# zok-atmega644-bob.net
KiCad netlist of a schematic drawn in EAGLE
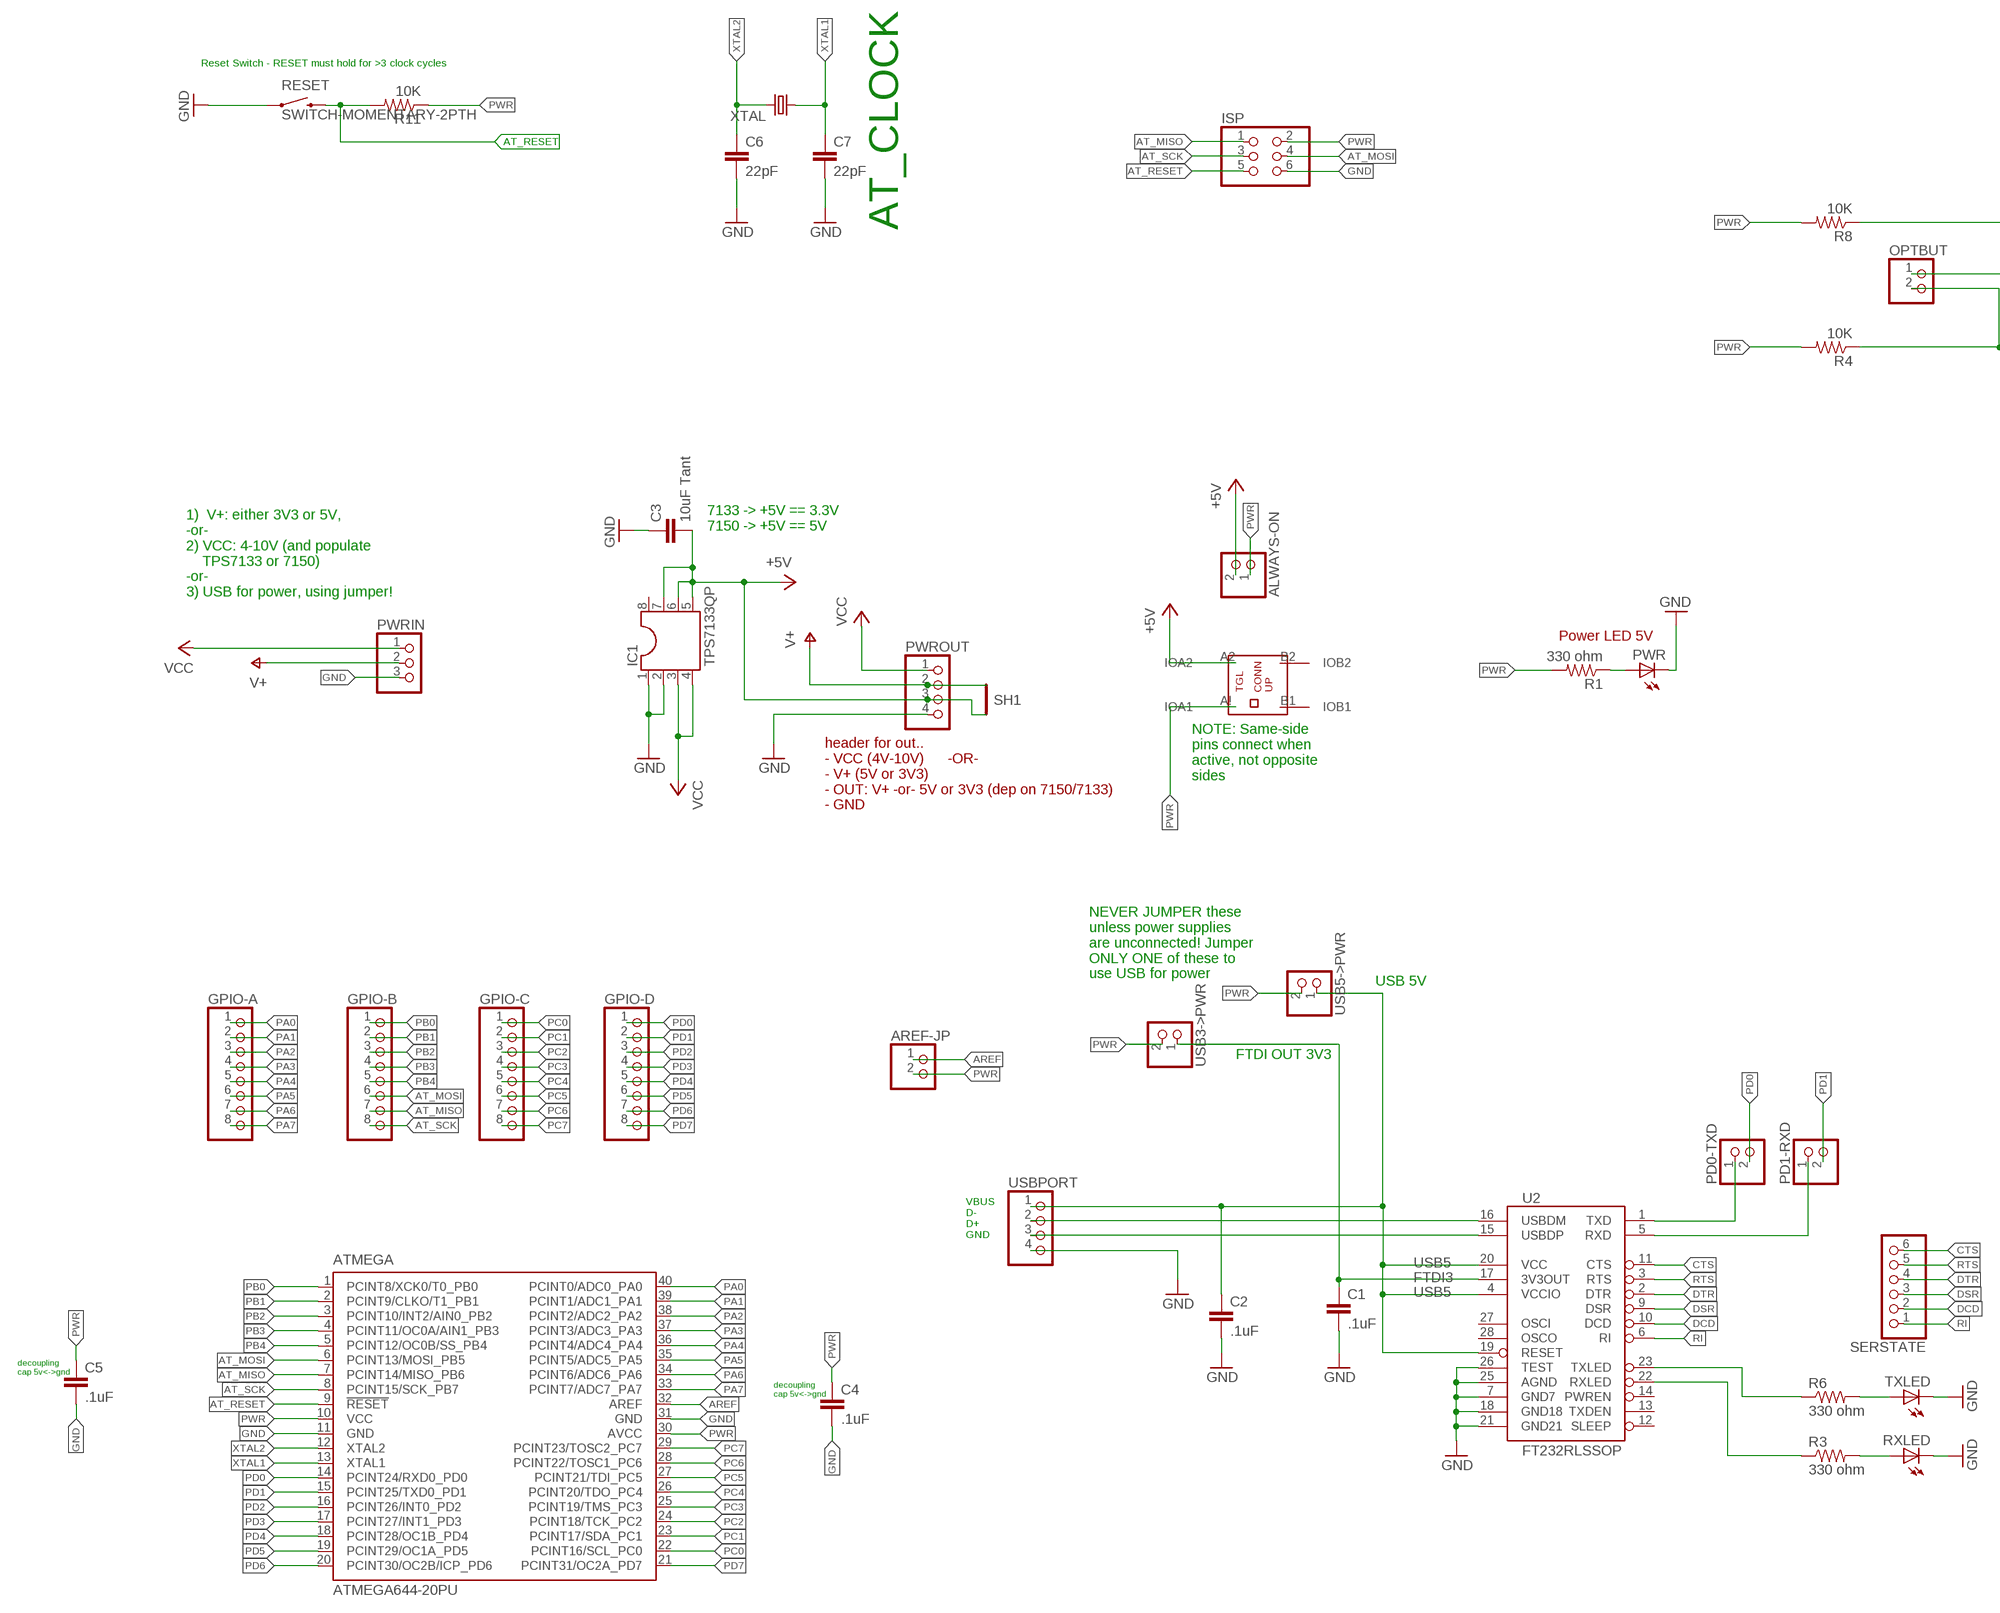
[diagram p0: schematic, sheet 1, part 1 of 2]
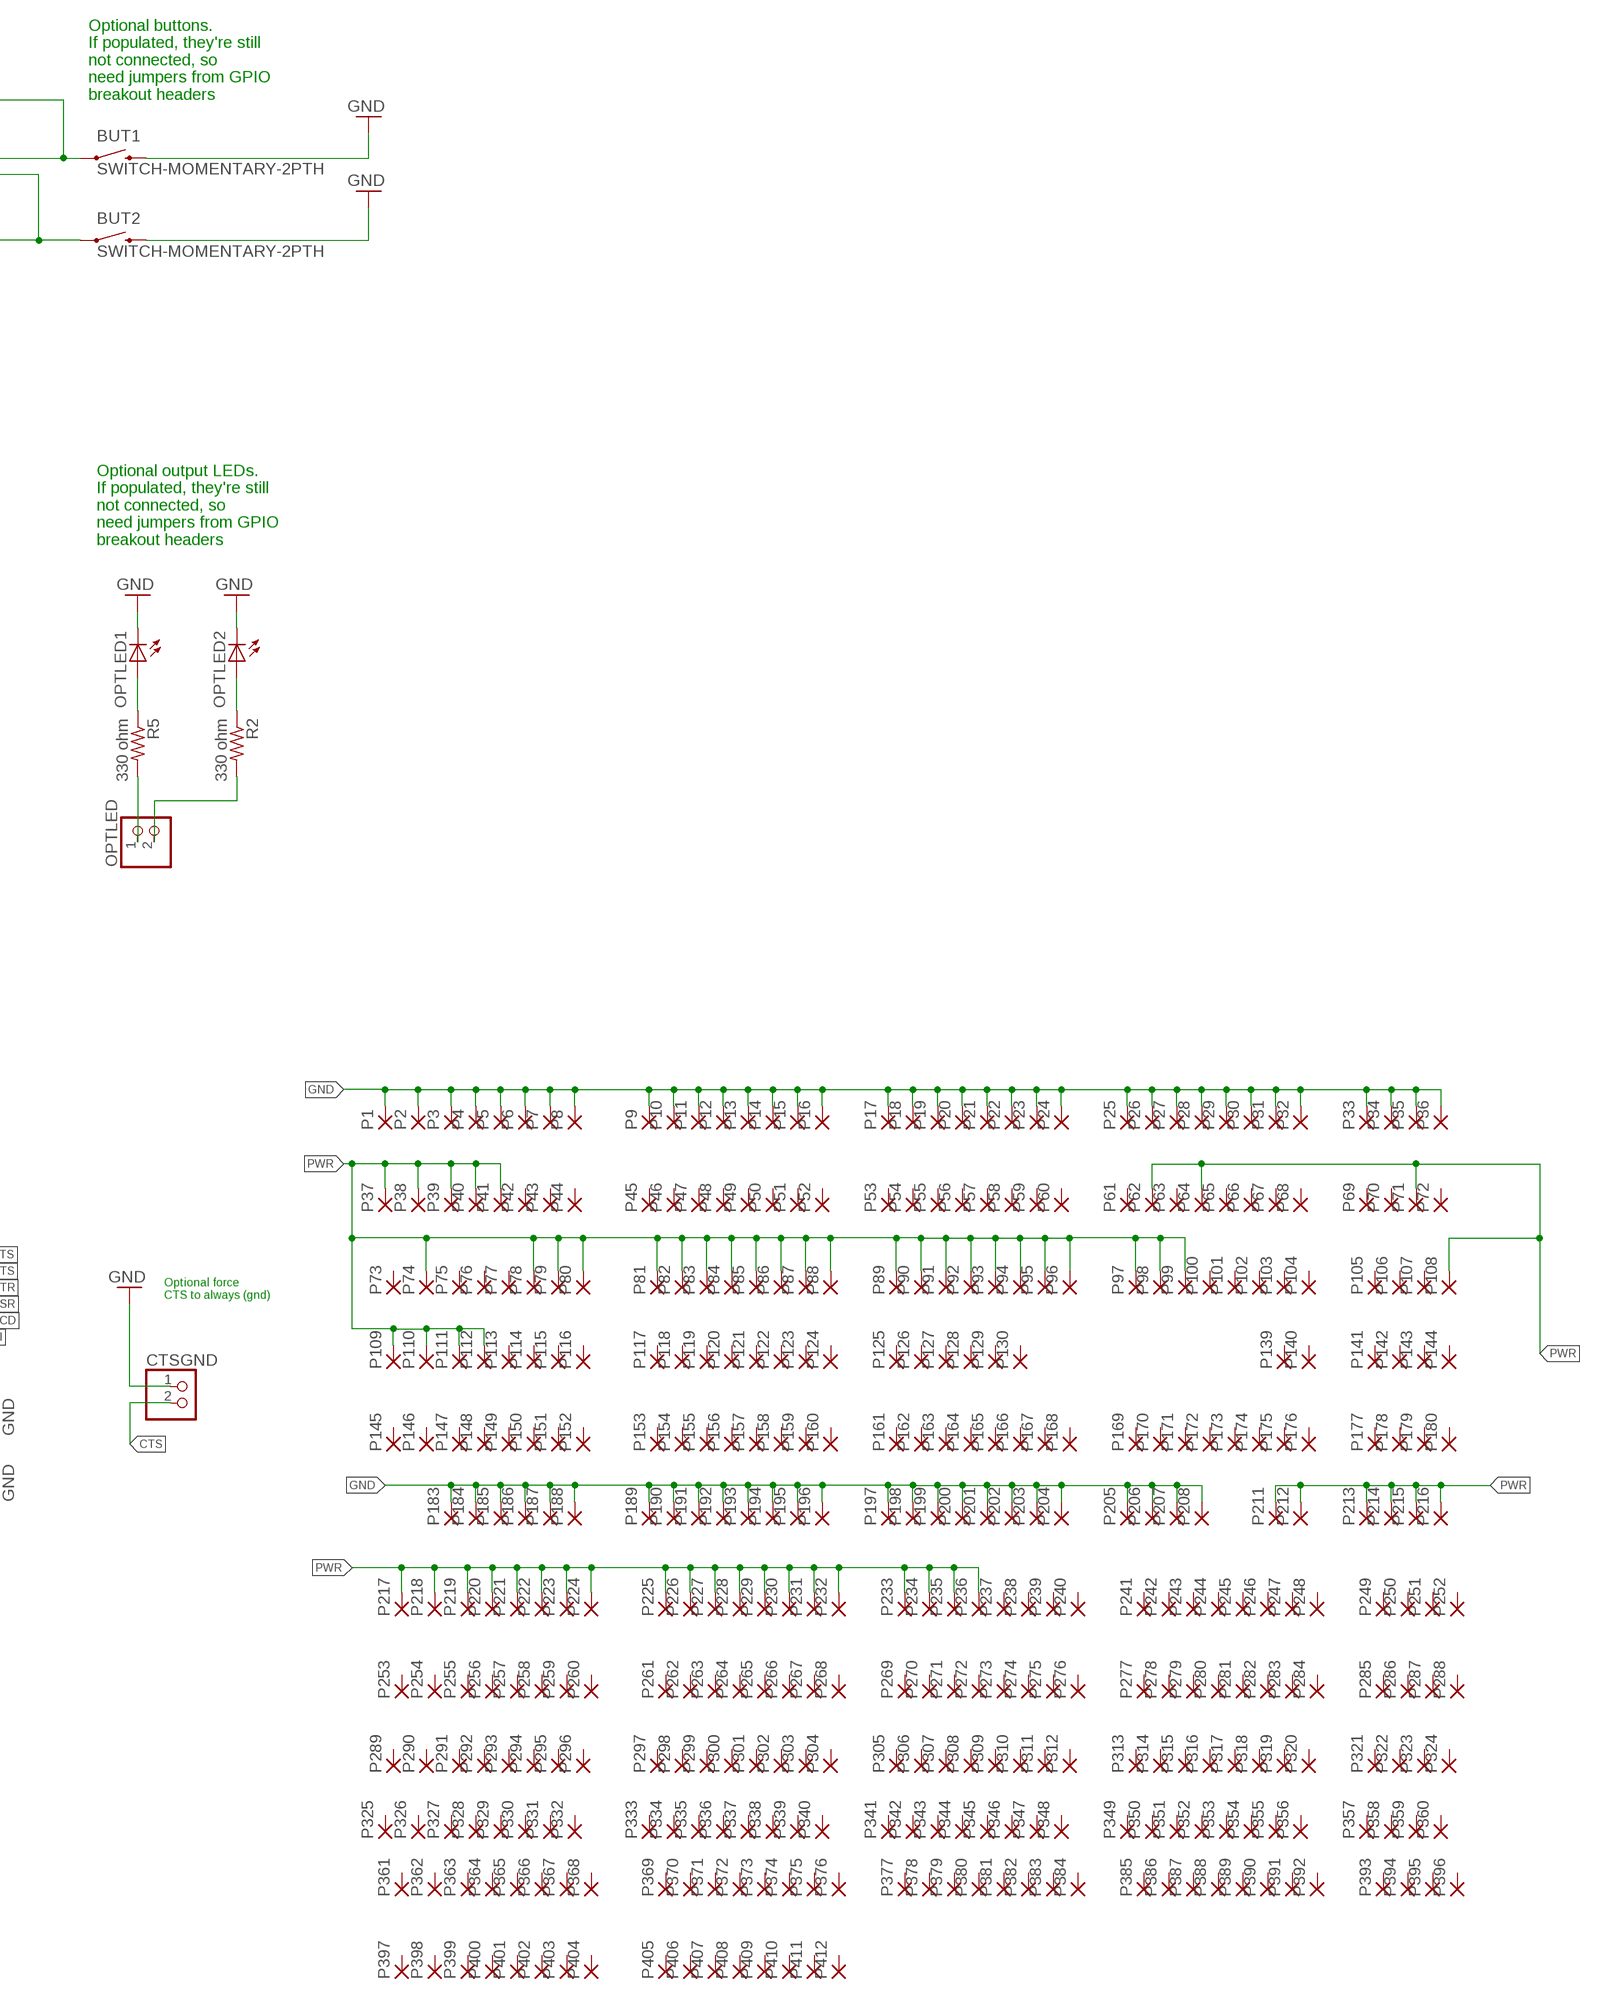
[diagram p1: schematic, sheet 1, part 2 of 2]

(export (version "E")
  (design (tool "Eeschema 10.0.6"))
  (components
    (comp (ref "ALWAYS-ON")
      (value "PINHD-1X2")
      (footprint "eagle-import:1X02")
      (libsource (lib "eagle-import") (part "PINHD-1X2"))
    )
    (comp (ref "AREF-JP")
      (value "PINHD-1X2")
      (footprint "eagle-import:1X02")
      (libsource (lib "eagle-import") (part "PINHD-1X2"))
    )
    (comp (ref "ATMEGA")
      (value "ATMEGA644-20PU")
      (footprint "eagle-import:DIL40")
      (libsource (lib "eagle-import") (part "ATMEGA644-PU20"))
    )
    (comp (ref "BUT1")
      (value "SWITCH-MOMENTARY-2PTH")
      (footprint "eagle-import:TACTILE-PTH")
      (libsource (lib "eagle-import") (part "SWITCH-MOMENTARY-2PTH"))
    )
    (comp (ref "BUT2")
      (value "SWITCH-MOMENTARY-2PTH")
      (footprint "eagle-import:TACTILE-PTH")
      (libsource (lib "eagle-import") (part "SWITCH-MOMENTARY-2PTH"))
    )
    (comp (ref "C1")
      (value ".1uF")
      (footprint "eagle-import:C025-025X050")
      (libsource (lib "eagle-import") (part "C-EU025-025X050"))
    )
    (comp (ref "C2")
      (value ".1uF")
      (footprint "eagle-import:C025-025X050")
      (libsource (lib "eagle-import") (part "C-EU025-025X050"))
    )
    (comp (ref "C3")
      (value "10uF Tant")
      (footprint "eagle-import:C025-025X050")
      (libsource (lib "eagle-import") (part "C-EU025-025X050"))
    )
    (comp (ref "C4")
      (value ".1uF")
      (footprint "eagle-import:C025-025X050")
      (libsource (lib "eagle-import") (part "C-EU025-025X050"))
    )
    (comp (ref "C5")
      (value ".1uF")
      (footprint "eagle-import:C025-025X050")
      (libsource (lib "eagle-import") (part "C-EU025-025X050"))
    )
    (comp (ref "C6")
      (value "22pF")
      (footprint "eagle-import:C025-025X050")
      (libsource (lib "eagle-import") (part "C-EU025-025X050"))
    )
    (comp (ref "C7")
      (value "22pF")
      (footprint "eagle-import:C025-025X050")
      (libsource (lib "eagle-import") (part "C-EU025-025X050"))
    )
    (comp (ref "CTSGND")
      (value "PINHD-1X2")
      (footprint "eagle-import:1X02")
      (libsource (lib "eagle-import") (part "PINHD-1X2"))
    )
    (comp (ref "GPIO-A")
      (value "PINHD-1X8")
      (footprint "eagle-import:1X08")
      (libsource (lib "eagle-import") (part "PINHD-1X8"))
    )
    (comp (ref "GPIO-B")
      (value "PINHD-1X8")
      (footprint "eagle-import:1X08")
      (libsource (lib "eagle-import") (part "PINHD-1X8"))
    )
    (comp (ref "GPIO-C")
      (value "PINHD-1X8")
      (footprint "eagle-import:1X08")
      (libsource (lib "eagle-import") (part "PINHD-1X8"))
    )
    (comp (ref "GPIO-D")
      (value "PINHD-1X8")
      (footprint "eagle-import:1X08")
      (libsource (lib "eagle-import") (part "PINHD-1X8"))
    )
    (comp (ref "IC1")
      (value "TPS7133QP")
      (footprint "eagle-import:DIL08")
      (libsource (lib "eagle-import") (part "DIL8"))
    )
    (comp (ref "ISP")
      (value "PINHD-2X3")
      (footprint "eagle-import:2X03")
      (libsource (lib "eagle-import") (part "PINHD-2X3"))
    )
    (comp (ref "OPTBUT")
      (value "PINHD-1X2")
      (footprint "eagle-import:1X02")
      (libsource (lib "eagle-import") (part "PINHD-1X2"))
    )
    (comp (ref "OPTLED")
      (value "PINHD-1X2")
      (footprint "eagle-import:1X02")
      (libsource (lib "eagle-import") (part "PINHD-1X2"))
    )
    (comp (ref "OPTLED1")
      (value "LED5MM")
      (footprint "eagle-import:LED5MM")
      (libsource (lib "eagle-import") (part "LED5MM"))
    )
    (comp (ref "OPTLED2")
      (value "LED5MM")
      (footprint "eagle-import:LED5MM")
      (libsource (lib "eagle-import") (part "LED5MM"))
    )
    (comp (ref "P1")
      (value "1,6/0,9")
      (footprint "eagle-import:1,6_0,9")
      (libsource (lib "eagle-import") (part "1,6/0,9"))
    )
    (comp (ref "P2")
      (value "1,6/0,9")
      (footprint "eagle-import:1,6_0,9")
      (libsource (lib "eagle-import") (part "1,6/0,9"))
    )
    (comp (ref "P3")
      (value "1,6/0,9")
      (footprint "eagle-import:1,6_0,9")
      (libsource (lib "eagle-import") (part "1,6/0,9"))
    )
    (comp (ref "P4")
      (value "1,6/0,9")
      (footprint "eagle-import:1,6_0,9")
      (libsource (lib "eagle-import") (part "1,6/0,9"))
    )
    (comp (ref "P5")
      (value "1,6/0,9")
      (footprint "eagle-import:1,6_0,9")
      (libsource (lib "eagle-import") (part "1,6/0,9"))
    )
    (comp (ref "P6")
      (value "1,6/0,9")
      (footprint "eagle-import:1,6_0,9")
      (libsource (lib "eagle-import") (part "1,6/0,9"))
    )
    (comp (ref "P7")
      (value "1,6/0,9")
      (footprint "eagle-import:1,6_0,9")
      (libsource (lib "eagle-import") (part "1,6/0,9"))
    )
    (comp (ref "P8")
      (value "1,6/0,9")
      (footprint "eagle-import:1,6_0,9")
      (libsource (lib "eagle-import") (part "1,6/0,9"))
    )
    (comp (ref "P9")
      (value "1,6/0,9")
      (footprint "eagle-import:1,6_0,9")
      (libsource (lib "eagle-import") (part "1,6/0,9"))
    )
    (comp (ref "P10")
      (value "1,6/0,9")
      (footprint "eagle-import:1,6_0,9")
      (libsource (lib "eagle-import") (part "1,6/0,9"))
    )
    (comp (ref "P11")
      (value "1,6/0,9")
      (footprint "eagle-import:1,6_0,9")
      (libsource (lib "eagle-import") (part "1,6/0,9"))
    )
    (comp (ref "P12")
      (value "1,6/0,9")
      (footprint "eagle-import:1,6_0,9")
      (libsource (lib "eagle-import") (part "1,6/0,9"))
    )
    (comp (ref "P13")
      (value "1,6/0,9")
      (footprint "eagle-import:1,6_0,9")
      (libsource (lib "eagle-import") (part "1,6/0,9"))
    )
    (comp (ref "P14")
      (value "1,6/0,9")
      (footprint "eagle-import:1,6_0,9")
      (libsource (lib "eagle-import") (part "1,6/0,9"))
    )
    (comp (ref "P15")
      (value "1,6/0,9")
      (footprint "eagle-import:1,6_0,9")
      (libsource (lib "eagle-import") (part "1,6/0,9"))
    )
    (comp (ref "P16")
      (value "1,6/0,9")
      (footprint "eagle-import:1,6_0,9")
      (libsource (lib "eagle-import") (part "1,6/0,9"))
    )
    (comp (ref "P17")
      (value "1,6/0,9")
      (footprint "eagle-import:1,6_0,9")
      (libsource (lib "eagle-import") (part "1,6/0,9"))
    )
    (comp (ref "P18")
      (value "1,6/0,9")
      (footprint "eagle-import:1,6_0,9")
      (libsource (lib "eagle-import") (part "1,6/0,9"))
    )
    (comp (ref "P19")
      (value "1,6/0,9")
      (footprint "eagle-import:1,6_0,9")
      (libsource (lib "eagle-import") (part "1,6/0,9"))
    )
    (comp (ref "P20")
      (value "1,6/0,9")
      (footprint "eagle-import:1,6_0,9")
      (libsource (lib "eagle-import") (part "1,6/0,9"))
    )
    (comp (ref "P21")
      (value "1,6/0,9")
      (footprint "eagle-import:1,6_0,9")
      (libsource (lib "eagle-import") (part "1,6/0,9"))
    )
    (comp (ref "P22")
      (value "1,6/0,9")
      (footprint "eagle-import:1,6_0,9")
      (libsource (lib "eagle-import") (part "1,6/0,9"))
    )
    (comp (ref "P23")
      (value "1,6/0,9")
      (footprint "eagle-import:1,6_0,9")
      (libsource (lib "eagle-import") (part "1,6/0,9"))
    )
    (comp (ref "P24")
      (value "1,6/0,9")
      (footprint "eagle-import:1,6_0,9")
      (libsource (lib "eagle-import") (part "1,6/0,9"))
    )
    (comp (ref "P25")
      (value "1,6/0,9")
      (footprint "eagle-import:1,6_0,9")
      (libsource (lib "eagle-import") (part "1,6/0,9"))
    )
    (comp (ref "P26")
      (value "1,6/0,9")
      (footprint "eagle-import:1,6_0,9")
      (libsource (lib "eagle-import") (part "1,6/0,9"))
    )
    (comp (ref "P27")
      (value "1,6/0,9")
      (footprint "eagle-import:1,6_0,9")
      (libsource (lib "eagle-import") (part "1,6/0,9"))
    )
    (comp (ref "P28")
      (value "1,6/0,9")
      (footprint "eagle-import:1,6_0,9")
      (libsource (lib "eagle-import") (part "1,6/0,9"))
    )
    (comp (ref "P29")
      (value "1,6/0,9")
      (footprint "eagle-import:1,6_0,9")
      (libsource (lib "eagle-import") (part "1,6/0,9"))
    )
    (comp (ref "P30")
      (value "1,6/0,9")
      (footprint "eagle-import:1,6_0,9")
      (libsource (lib "eagle-import") (part "1,6/0,9"))
    )
    (comp (ref "P31")
      (value "1,6/0,9")
      (footprint "eagle-import:1,6_0,9")
      (libsource (lib "eagle-import") (part "1,6/0,9"))
    )
    (comp (ref "P32")
      (value "1,6/0,9")
      (footprint "eagle-import:1,6_0,9")
      (libsource (lib "eagle-import") (part "1,6/0,9"))
    )
    (comp (ref "P33")
      (value "1,6/0,9")
      (footprint "eagle-import:1,6_0,9")
      (libsource (lib "eagle-import") (part "1,6/0,9"))
    )
    (comp (ref "P34")
      (value "1,6/0,9")
      (footprint "eagle-import:1,6_0,9")
      (libsource (lib "eagle-import") (part "1,6/0,9"))
    )
    (comp (ref "P35")
      (value "1,6/0,9")
      (footprint "eagle-import:1,6_0,9")
      (libsource (lib "eagle-import") (part "1,6/0,9"))
    )
    (comp (ref "P36")
      (value "1,6/0,9")
      (footprint "eagle-import:1,6_0,9")
      (libsource (lib "eagle-import") (part "1,6/0,9"))
    )
    (comp (ref "P37")
      (value "1,6/0,9")
      (footprint "eagle-import:1,6_0,9")
      (libsource (lib "eagle-import") (part "1,6/0,9"))
    )
    (comp (ref "P38")
      (value "1,6/0,9")
      (footprint "eagle-import:1,6_0,9")
      (libsource (lib "eagle-import") (part "1,6/0,9"))
    )
    (comp (ref "P39")
      (value "1,6/0,9")
      (footprint "eagle-import:1,6_0,9")
      (libsource (lib "eagle-import") (part "1,6/0,9"))
    )
    (comp (ref "P40")
      (value "1,6/0,9")
      (footprint "eagle-import:1,6_0,9")
      (libsource (lib "eagle-import") (part "1,6/0,9"))
    )
    (comp (ref "P41")
      (value "1,6/0,9")
      (footprint "eagle-import:1,6_0,9")
      (libsource (lib "eagle-import") (part "1,6/0,9"))
    )
    (comp (ref "P42")
      (value "1,6/0,9")
      (footprint "eagle-import:1,6_0,9")
      (libsource (lib "eagle-import") (part "1,6/0,9"))
    )
    (comp (ref "P43")
      (value "1,6/0,9")
      (footprint "eagle-import:1,6_0,9")
      (libsource (lib "eagle-import") (part "1,6/0,9"))
    )
    (comp (ref "P44")
      (value "1,6/0,9")
      (footprint "eagle-import:1,6_0,9")
      (libsource (lib "eagle-import") (part "1,6/0,9"))
    )
    (comp (ref "P45")
      (value "1,6/0,9")
      (footprint "eagle-import:1,6_0,9")
      (libsource (lib "eagle-import") (part "1,6/0,9"))
    )
    (comp (ref "P46")
      (value "1,6/0,9")
      (footprint "eagle-import:1,6_0,9")
      (libsource (lib "eagle-import") (part "1,6/0,9"))
    )
    (comp (ref "P47")
      (value "1,6/0,9")
      (footprint "eagle-import:1,6_0,9")
      (libsource (lib "eagle-import") (part "1,6/0,9"))
    )
    (comp (ref "P48")
      (value "1,6/0,9")
      (footprint "eagle-import:1,6_0,9")
      (libsource (lib "eagle-import") (part "1,6/0,9"))
    )
    (comp (ref "P49")
      (value "1,6/0,9")
      (footprint "eagle-import:1,6_0,9")
      (libsource (lib "eagle-import") (part "1,6/0,9"))
    )
    (comp (ref "P50")
      (value "1,6/0,9")
      (footprint "eagle-import:1,6_0,9")
      (libsource (lib "eagle-import") (part "1,6/0,9"))
    )
    (comp (ref "P51")
      (value "1,6/0,9")
      (footprint "eagle-import:1,6_0,9")
      (libsource (lib "eagle-import") (part "1,6/0,9"))
    )
    (comp (ref "P52")
      (value "1,6/0,9")
      (footprint "eagle-import:1,6_0,9")
      (libsource (lib "eagle-import") (part "1,6/0,9"))
    )
    (comp (ref "P53")
      (value "1,6/0,9")
      (footprint "eagle-import:1,6_0,9")
      (libsource (lib "eagle-import") (part "1,6/0,9"))
    )
    (comp (ref "P54")
      (value "1,6/0,9")
      (footprint "eagle-import:1,6_0,9")
      (libsource (lib "eagle-import") (part "1,6/0,9"))
    )
    (comp (ref "P55")
      (value "1,6/0,9")
      (footprint "eagle-import:1,6_0,9")
      (libsource (lib "eagle-import") (part "1,6/0,9"))
    )
    (comp (ref "P56")
      (value "1,6/0,9")
      (footprint "eagle-import:1,6_0,9")
      (libsource (lib "eagle-import") (part "1,6/0,9"))
    )
    (comp (ref "P57")
      (value "1,6/0,9")
      (footprint "eagle-import:1,6_0,9")
      (libsource (lib "eagle-import") (part "1,6/0,9"))
    )
    (comp (ref "P58")
      (value "1,6/0,9")
      (footprint "eagle-import:1,6_0,9")
      (libsource (lib "eagle-import") (part "1,6/0,9"))
    )
    (comp (ref "P59")
      (value "1,6/0,9")
      (footprint "eagle-import:1,6_0,9")
      (libsource (lib "eagle-import") (part "1,6/0,9"))
    )
    (comp (ref "P60")
      (value "1,6/0,9")
      (footprint "eagle-import:1,6_0,9")
      (libsource (lib "eagle-import") (part "1,6/0,9"))
    )
    (comp (ref "P61")
      (value "1,6/0,9")
      (footprint "eagle-import:1,6_0,9")
      (libsource (lib "eagle-import") (part "1,6/0,9"))
    )
    (comp (ref "P62")
      (value "1,6/0,9")
      (footprint "eagle-import:1,6_0,9")
      (libsource (lib "eagle-import") (part "1,6/0,9"))
    )
    (comp (ref "P63")
      (value "1,6/0,9")
      (footprint "eagle-import:1,6_0,9")
      (libsource (lib "eagle-import") (part "1,6/0,9"))
    )
    (comp (ref "P64")
      (value "1,6/0,9")
      (footprint "eagle-import:1,6_0,9")
      (libsource (lib "eagle-import") (part "1,6/0,9"))
    )
    (comp (ref "P65")
      (value "1,6/0,9")
      (footprint "eagle-import:1,6_0,9")
      (libsource (lib "eagle-import") (part "1,6/0,9"))
    )
    (comp (ref "P66")
      (value "1,6/0,9")
      (footprint "eagle-import:1,6_0,9")
      (libsource (lib "eagle-import") (part "1,6/0,9"))
    )
    (comp (ref "P67")
      (value "1,6/0,9")
      (footprint "eagle-import:1,6_0,9")
      (libsource (lib "eagle-import") (part "1,6/0,9"))
    )
    (comp (ref "P68")
      (value "1,6/0,9")
      (footprint "eagle-import:1,6_0,9")
      (libsource (lib "eagle-import") (part "1,6/0,9"))
    )
    (comp (ref "P69")
      (value "1,6/0,9")
      (footprint "eagle-import:1,6_0,9")
      (libsource (lib "eagle-import") (part "1,6/0,9"))
    )
    (comp (ref "P70")
      (value "1,6/0,9")
      (footprint "eagle-import:1,6_0,9")
      (libsource (lib "eagle-import") (part "1,6/0,9"))
    )
    (comp (ref "P71")
      (value "1,6/0,9")
      (footprint "eagle-import:1,6_0,9")
      (libsource (lib "eagle-import") (part "1,6/0,9"))
    )
    (comp (ref "P72")
      (value "1,6/0,9")
      (footprint "eagle-import:1,6_0,9")
      (libsource (lib "eagle-import") (part "1,6/0,9"))
    )
    (comp (ref "P73")
      (value "1,6/0,9")
      (footprint "eagle-import:1,6_0,9")
      (libsource (lib "eagle-import") (part "1,6/0,9"))
    )
    (comp (ref "P74")
      (value "1,6/0,9")
      (footprint "eagle-import:1,6_0,9")
      (libsource (lib "eagle-import") (part "1,6/0,9"))
    )
    (comp (ref "P75")
      (value "1,6/0,9")
      (footprint "eagle-import:1,6_0,9")
      (libsource (lib "eagle-import") (part "1,6/0,9"))
    )
    (comp (ref "P76")
      (value "1,6/0,9")
      (footprint "eagle-import:1,6_0,9")
      (libsource (lib "eagle-import") (part "1,6/0,9"))
    )
    (comp (ref "P77")
      (value "1,6/0,9")
      (footprint "eagle-import:1,6_0,9")
      (libsource (lib "eagle-import") (part "1,6/0,9"))
    )
    (comp (ref "P78")
      (value "1,6/0,9")
      (footprint "eagle-import:1,6_0,9")
      (libsource (lib "eagle-import") (part "1,6/0,9"))
    )
    (comp (ref "P79")
      (value "1,6/0,9")
      (footprint "eagle-import:1,6_0,9")
      (libsource (lib "eagle-import") (part "1,6/0,9"))
    )
    (comp (ref "P80")
      (value "1,6/0,9")
      (footprint "eagle-import:1,6_0,9")
      (libsource (lib "eagle-import") (part "1,6/0,9"))
    )
    (comp (ref "P81")
      (value "1,6/0,9")
      (footprint "eagle-import:1,6_0,9")
      (libsource (lib "eagle-import") (part "1,6/0,9"))
    )
    (comp (ref "P82")
      (value "1,6/0,9")
      (footprint "eagle-import:1,6_0,9")
      (libsource (lib "eagle-import") (part "1,6/0,9"))
    )
    (comp (ref "P83")
      (value "1,6/0,9")
      (footprint "eagle-import:1,6_0,9")
      (libsource (lib "eagle-import") (part "1,6/0,9"))
    )
    (comp (ref "P84")
      (value "1,6/0,9")
      (footprint "eagle-import:1,6_0,9")
      (libsource (lib "eagle-import") (part "1,6/0,9"))
    )
    (comp (ref "P85")
      (value "1,6/0,9")
      (footprint "eagle-import:1,6_0,9")
      (libsource (lib "eagle-import") (part "1,6/0,9"))
    )
    (comp (ref "P86")
      (value "1,6/0,9")
      (footprint "eagle-import:1,6_0,9")
      (libsource (lib "eagle-import") (part "1,6/0,9"))
    )
    (comp (ref "P87")
      (value "1,6/0,9")
      (footprint "eagle-import:1,6_0,9")
      (libsource (lib "eagle-import") (part "1,6/0,9"))
    )
    (comp (ref "P88")
      (value "1,6/0,9")
      (footprint "eagle-import:1,6_0,9")
      (libsource (lib "eagle-import") (part "1,6/0,9"))
    )
    (comp (ref "P89")
      (value "1,6/0,9")
      (footprint "eagle-import:1,6_0,9")
      (libsource (lib "eagle-import") (part "1,6/0,9"))
    )
    (comp (ref "P90")
      (value "1,6/0,9")
      (footprint "eagle-import:1,6_0,9")
      (libsource (lib "eagle-import") (part "1,6/0,9"))
    )
    (comp (ref "P91")
      (value "1,6/0,9")
      (footprint "eagle-import:1,6_0,9")
      (libsource (lib "eagle-import") (part "1,6/0,9"))
    )
    (comp (ref "P92")
      (value "1,6/0,9")
      (footprint "eagle-import:1,6_0,9")
      (libsource (lib "eagle-import") (part "1,6/0,9"))
    )
    (comp (ref "P93")
      (value "1,6/0,9")
      (footprint "eagle-import:1,6_0,9")
      (libsource (lib "eagle-import") (part "1,6/0,9"))
    )
    (comp (ref "P94")
      (value "1,6/0,9")
      (footprint "eagle-import:1,6_0,9")
      (libsource (lib "eagle-import") (part "1,6/0,9"))
    )
    (comp (ref "P95")
      (value "1,6/0,9")
      (footprint "eagle-import:1,6_0,9")
      (libsource (lib "eagle-import") (part "1,6/0,9"))
    )
    (comp (ref "P96")
      (value "1,6/0,9")
      (footprint "eagle-import:1,6_0,9")
      (libsource (lib "eagle-import") (part "1,6/0,9"))
    )
    (comp (ref "P97")
      (value "1,6/0,9")
      (footprint "eagle-import:1,6_0,9")
      (libsource (lib "eagle-import") (part "1,6/0,9"))
    )
    (comp (ref "P98")
      (value "1,6/0,9")
      (footprint "eagle-import:1,6_0,9")
      (libsource (lib "eagle-import") (part "1,6/0,9"))
    )
    (comp (ref "P99")
      (value "1,6/0,9")
      (footprint "eagle-import:1,6_0,9")
      (libsource (lib "eagle-import") (part "1,6/0,9"))
    )
    (comp (ref "P100")
      (value "1,6/0,9")
      (footprint "eagle-import:1,6_0,9")
      (libsource (lib "eagle-import") (part "1,6/0,9"))
    )
    (comp (ref "P101")
      (value "1,6/0,9")
      (footprint "eagle-import:1,6_0,9")
      (libsource (lib "eagle-import") (part "1,6/0,9"))
    )
    (comp (ref "P102")
      (value "1,6/0,9")
      (footprint "eagle-import:1,6_0,9")
      (libsource (lib "eagle-import") (part "1,6/0,9"))
    )
    (comp (ref "P103")
      (value "1,6/0,9")
      (footprint "eagle-import:1,6_0,9")
      (libsource (lib "eagle-import") (part "1,6/0,9"))
    )
    (comp (ref "P104")
      (value "1,6/0,9")
      (footprint "eagle-import:1,6_0,9")
      (libsource (lib "eagle-import") (part "1,6/0,9"))
    )
    (comp (ref "P105")
      (value "1,6/0,9")
      (footprint "eagle-import:1,6_0,9")
      (libsource (lib "eagle-import") (part "1,6/0,9"))
    )
    (comp (ref "P106")
      (value "1,6/0,9")
      (footprint "eagle-import:1,6_0,9")
      (libsource (lib "eagle-import") (part "1,6/0,9"))
    )
    (comp (ref "P107")
      (value "1,6/0,9")
      (footprint "eagle-import:1,6_0,9")
      (libsource (lib "eagle-import") (part "1,6/0,9"))
    )
    (comp (ref "P108")
      (value "1,6/0,9")
      (footprint "eagle-import:1,6_0,9")
      (libsource (lib "eagle-import") (part "1,6/0,9"))
    )
    (comp (ref "P109")
      (value "1,6/0,9")
      (footprint "eagle-import:1,6_0,9")
      (libsource (lib "eagle-import") (part "1,6/0,9"))
    )
    (comp (ref "P110")
      (value "1,6/0,9")
      (footprint "eagle-import:1,6_0,9")
      (libsource (lib "eagle-import") (part "1,6/0,9"))
    )
    (comp (ref "P111")
      (value "1,6/0,9")
      (footprint "eagle-import:1,6_0,9")
      (libsource (lib "eagle-import") (part "1,6/0,9"))
    )
    (comp (ref "P112")
      (value "1,6/0,9")
      (footprint "eagle-import:1,6_0,9")
      (libsource (lib "eagle-import") (part "1,6/0,9"))
    )
    (comp (ref "P113")
      (value "1,6/0,9")
      (footprint "eagle-import:1,6_0,9")
      (libsource (lib "eagle-import") (part "1,6/0,9"))
    )
    (comp (ref "P114")
      (value "1,6/0,9")
      (footprint "eagle-import:1,6_0,9")
      (libsource (lib "eagle-import") (part "1,6/0,9"))
    )
    (comp (ref "P115")
      (value "1,6/0,9")
      (footprint "eagle-import:1,6_0,9")
      (libsource (lib "eagle-import") (part "1,6/0,9"))
    )
    (comp (ref "P116")
      (value "1,6/0,9")
      (footprint "eagle-import:1,6_0,9")
      (libsource (lib "eagle-import") (part "1,6/0,9"))
    )
    (comp (ref "P117")
      (value "1,6/0,9")
      (footprint "eagle-import:1,6_0,9")
      (libsource (lib "eagle-import") (part "1,6/0,9"))
    )
    (comp (ref "P118")
      (value "1,6/0,9")
      (footprint "eagle-import:1,6_0,9")
      (libsource (lib "eagle-import") (part "1,6/0,9"))
    )
    (comp (ref "P119")
      (value "1,6/0,9")
      (footprint "eagle-import:1,6_0,9")
      (libsource (lib "eagle-import") (part "1,6/0,9"))
    )
    (comp (ref "P120")
      (value "1,6/0,9")
      (footprint "eagle-import:1,6_0,9")
      (libsource (lib "eagle-import") (part "1,6/0,9"))
    )
    (comp (ref "P121")
      (value "1,6/0,9")
      (footprint "eagle-import:1,6_0,9")
      (libsource (lib "eagle-import") (part "1,6/0,9"))
    )
    (comp (ref "P122")
      (value "1,6/0,9")
      (footprint "eagle-import:1,6_0,9")
      (libsource (lib "eagle-import") (part "1,6/0,9"))
    )
    (comp (ref "P123")
      (value "1,6/0,9")
      (footprint "eagle-import:1,6_0,9")
      (libsource (lib "eagle-import") (part "1,6/0,9"))
    )
    (comp (ref "P124")
      (value "1,6/0,9")
      (footprint "eagle-import:1,6_0,9")
      (libsource (lib "eagle-import") (part "1,6/0,9"))
    )
    (comp (ref "P125")
      (value "1,6/0,9")
      (footprint "eagle-import:1,6_0,9")
      (libsource (lib "eagle-import") (part "1,6/0,9"))
    )
    (comp (ref "P126")
      (value "1,6/0,9")
      (footprint "eagle-import:1,6_0,9")
      (libsource (lib "eagle-import") (part "1,6/0,9"))
    )
    (comp (ref "P127")
      (value "1,6/0,9")
      (footprint "eagle-import:1,6_0,9")
      (libsource (lib "eagle-import") (part "1,6/0,9"))
    )
    (comp (ref "P128")
      (value "1,6/0,9")
      (footprint "eagle-import:1,6_0,9")
      (libsource (lib "eagle-import") (part "1,6/0,9"))
    )
    (comp (ref "P129")
      (value "1,6/0,9")
      (footprint "eagle-import:1,6_0,9")
      (libsource (lib "eagle-import") (part "1,6/0,9"))
    )
    (comp (ref "P130")
      (value "1,6/0,9")
      (footprint "eagle-import:1,6_0,9")
      (libsource (lib "eagle-import") (part "1,6/0,9"))
    )
    (comp (ref "P139")
      (value "1,6/0,9")
      (footprint "eagle-import:1,6_0,9")
      (libsource (lib "eagle-import") (part "1,6/0,9"))
    )
    (comp (ref "P140")
      (value "1,6/0,9")
      (footprint "eagle-import:1,6_0,9")
      (libsource (lib "eagle-import") (part "1,6/0,9"))
    )
    (comp (ref "P141")
      (value "1,6/0,9")
      (footprint "eagle-import:1,6_0,9")
      (libsource (lib "eagle-import") (part "1,6/0,9"))
    )
    (comp (ref "P142")
      (value "1,6/0,9")
      (footprint "eagle-import:1,6_0,9")
      (libsource (lib "eagle-import") (part "1,6/0,9"))
    )
    (comp (ref "P143")
      (value "1,6/0,9")
      (footprint "eagle-import:1,6_0,9")
      (libsource (lib "eagle-import") (part "1,6/0,9"))
    )
    (comp (ref "P144")
      (value "1,6/0,9")
      (footprint "eagle-import:1,6_0,9")
      (libsource (lib "eagle-import") (part "1,6/0,9"))
    )
    (comp (ref "P145")
      (value "1,6/0,9")
      (footprint "eagle-import:1,6_0,9")
      (libsource (lib "eagle-import") (part "1,6/0,9"))
    )
    (comp (ref "P146")
      (value "1,6/0,9")
      (footprint "eagle-import:1,6_0,9")
      (libsource (lib "eagle-import") (part "1,6/0,9"))
    )
    (comp (ref "P147")
      (value "1,6/0,9")
      (footprint "eagle-import:1,6_0,9")
      (libsource (lib "eagle-import") (part "1,6/0,9"))
    )
    (comp (ref "P148")
      (value "1,6/0,9")
      (footprint "eagle-import:1,6_0,9")
      (libsource (lib "eagle-import") (part "1,6/0,9"))
    )
    (comp (ref "P149")
      (value "1,6/0,9")
      (footprint "eagle-import:1,6_0,9")
      (libsource (lib "eagle-import") (part "1,6/0,9"))
    )
    (comp (ref "P150")
      (value "1,6/0,9")
      (footprint "eagle-import:1,6_0,9")
      (libsource (lib "eagle-import") (part "1,6/0,9"))
    )
    (comp (ref "P151")
      (value "1,6/0,9")
      (footprint "eagle-import:1,6_0,9")
      (libsource (lib "eagle-import") (part "1,6/0,9"))
    )
    (comp (ref "P152")
      (value "1,6/0,9")
      (footprint "eagle-import:1,6_0,9")
      (libsource (lib "eagle-import") (part "1,6/0,9"))
    )
    (comp (ref "P153")
      (value "1,6/0,9")
      (footprint "eagle-import:1,6_0,9")
      (libsource (lib "eagle-import") (part "1,6/0,9"))
    )
    (comp (ref "P154")
      (value "1,6/0,9")
      (footprint "eagle-import:1,6_0,9")
      (libsource (lib "eagle-import") (part "1,6/0,9"))
    )
    (comp (ref "P155")
      (value "1,6/0,9")
      (footprint "eagle-import:1,6_0,9")
      (libsource (lib "eagle-import") (part "1,6/0,9"))
    )
    (comp (ref "P156")
      (value "1,6/0,9")
      (footprint "eagle-import:1,6_0,9")
      (libsource (lib "eagle-import") (part "1,6/0,9"))
    )
    (comp (ref "P157")
      (value "1,6/0,9")
      (footprint "eagle-import:1,6_0,9")
      (libsource (lib "eagle-import") (part "1,6/0,9"))
    )
    (comp (ref "P158")
      (value "1,6/0,9")
      (footprint "eagle-import:1,6_0,9")
      (libsource (lib "eagle-import") (part "1,6/0,9"))
    )
    (comp (ref "P159")
      (value "1,6/0,9")
      (footprint "eagle-import:1,6_0,9")
      (libsource (lib "eagle-import") (part "1,6/0,9"))
    )
    (comp (ref "P160")
      (value "1,6/0,9")
      (footprint "eagle-import:1,6_0,9")
      (libsource (lib "eagle-import") (part "1,6/0,9"))
    )
    (comp (ref "P161")
      (value "1,6/0,9")
      (footprint "eagle-import:1,6_0,9")
      (libsource (lib "eagle-import") (part "1,6/0,9"))
    )
    (comp (ref "P162")
      (value "1,6/0,9")
      (footprint "eagle-import:1,6_0,9")
      (libsource (lib "eagle-import") (part "1,6/0,9"))
    )
    (comp (ref "P163")
      (value "1,6/0,9")
      (footprint "eagle-import:1,6_0,9")
      (libsource (lib "eagle-import") (part "1,6/0,9"))
    )
    (comp (ref "P164")
      (value "1,6/0,9")
      (footprint "eagle-import:1,6_0,9")
      (libsource (lib "eagle-import") (part "1,6/0,9"))
    )
    (comp (ref "P165")
      (value "1,6/0,9")
      (footprint "eagle-import:1,6_0,9")
      (libsource (lib "eagle-import") (part "1,6/0,9"))
    )
    (comp (ref "P166")
      (value "1,6/0,9")
      (footprint "eagle-import:1,6_0,9")
      (libsource (lib "eagle-import") (part "1,6/0,9"))
    )
    (comp (ref "P167")
      (value "1,6/0,9")
      (footprint "eagle-import:1,6_0,9")
      (libsource (lib "eagle-import") (part "1,6/0,9"))
    )
    (comp (ref "P168")
      (value "1,6/0,9")
      (footprint "eagle-import:1,6_0,9")
      (libsource (lib "eagle-import") (part "1,6/0,9"))
    )
    (comp (ref "P169")
      (value "1,6/0,9")
      (footprint "eagle-import:1,6_0,9")
      (libsource (lib "eagle-import") (part "1,6/0,9"))
    )
    (comp (ref "P170")
      (value "1,6/0,9")
      (footprint "eagle-import:1,6_0,9")
      (libsource (lib "eagle-import") (part "1,6/0,9"))
    )
    (comp (ref "P171")
      (value "1,6/0,9")
      (footprint "eagle-import:1,6_0,9")
      (libsource (lib "eagle-import") (part "1,6/0,9"))
    )
    (comp (ref "P172")
      (value "1,6/0,9")
      (footprint "eagle-import:1,6_0,9")
      (libsource (lib "eagle-import") (part "1,6/0,9"))
    )
    (comp (ref "P173")
      (value "1,6/0,9")
      (footprint "eagle-import:1,6_0,9")
      (libsource (lib "eagle-import") (part "1,6/0,9"))
    )
    (comp (ref "P174")
      (value "1,6/0,9")
      (footprint "eagle-import:1,6_0,9")
      (libsource (lib "eagle-import") (part "1,6/0,9"))
    )
    (comp (ref "P175")
      (value "1,6/0,9")
      (footprint "eagle-import:1,6_0,9")
      (libsource (lib "eagle-import") (part "1,6/0,9"))
    )
    (comp (ref "P176")
      (value "1,6/0,9")
      (footprint "eagle-import:1,6_0,9")
      (libsource (lib "eagle-import") (part "1,6/0,9"))
    )
    (comp (ref "P177")
      (value "1,6/0,9")
      (footprint "eagle-import:1,6_0,9")
      (libsource (lib "eagle-import") (part "1,6/0,9"))
    )
    (comp (ref "P178")
      (value "1,6/0,9")
      (footprint "eagle-import:1,6_0,9")
      (libsource (lib "eagle-import") (part "1,6/0,9"))
    )
    (comp (ref "P179")
      (value "1,6/0,9")
      (footprint "eagle-import:1,6_0,9")
      (libsource (lib "eagle-import") (part "1,6/0,9"))
    )
    (comp (ref "P180")
      (value "1,6/0,9")
      (footprint "eagle-import:1,6_0,9")
      (libsource (lib "eagle-import") (part "1,6/0,9"))
    )
    (comp (ref "P183")
      (value "1,6/0,9")
      (footprint "eagle-import:1,6_0,9")
      (libsource (lib "eagle-import") (part "1,6/0,9"))
    )
    (comp (ref "P184")
      (value "1,6/0,9")
      (footprint "eagle-import:1,6_0,9")
      (libsource (lib "eagle-import") (part "1,6/0,9"))
    )
    (comp (ref "P185")
      (value "1,6/0,9")
      (footprint "eagle-import:1,6_0,9")
      (libsource (lib "eagle-import") (part "1,6/0,9"))
    )
    (comp (ref "P186")
      (value "1,6/0,9")
      (footprint "eagle-import:1,6_0,9")
      (libsource (lib "eagle-import") (part "1,6/0,9"))
    )
    (comp (ref "P187")
      (value "1,6/0,9")
      (footprint "eagle-import:1,6_0,9")
      (libsource (lib "eagle-import") (part "1,6/0,9"))
    )
    (comp (ref "P188")
      (value "1,6/0,9")
      (footprint "eagle-import:1,6_0,9")
      (libsource (lib "eagle-import") (part "1,6/0,9"))
    )
    (comp (ref "P189")
      (value "1,6/0,9")
      (footprint "eagle-import:1,6_0,9")
      (libsource (lib "eagle-import") (part "1,6/0,9"))
    )
    (comp (ref "P190")
      (value "1,6/0,9")
      (footprint "eagle-import:1,6_0,9")
      (libsource (lib "eagle-import") (part "1,6/0,9"))
    )
    (comp (ref "P191")
      (value "1,6/0,9")
      (footprint "eagle-import:1,6_0,9")
      (libsource (lib "eagle-import") (part "1,6/0,9"))
    )
    (comp (ref "P192")
      (value "1,6/0,9")
      (footprint "eagle-import:1,6_0,9")
      (libsource (lib "eagle-import") (part "1,6/0,9"))
    )
    (comp (ref "P193")
      (value "1,6/0,9")
      (footprint "eagle-import:1,6_0,9")
      (libsource (lib "eagle-import") (part "1,6/0,9"))
    )
    (comp (ref "P194")
      (value "1,6/0,9")
      (footprint "eagle-import:1,6_0,9")
      (libsource (lib "eagle-import") (part "1,6/0,9"))
    )
    (comp (ref "P195")
      (value "1,6/0,9")
      (footprint "eagle-import:1,6_0,9")
      (libsource (lib "eagle-import") (part "1,6/0,9"))
    )
    (comp (ref "P196")
      (value "1,6/0,9")
      (footprint "eagle-import:1,6_0,9")
      (libsource (lib "eagle-import") (part "1,6/0,9"))
    )
    (comp (ref "P197")
      (value "1,6/0,9")
      (footprint "eagle-import:1,6_0,9")
      (libsource (lib "eagle-import") (part "1,6/0,9"))
    )
    (comp (ref "P198")
      (value "1,6/0,9")
      (footprint "eagle-import:1,6_0,9")
      (libsource (lib "eagle-import") (part "1,6/0,9"))
    )
    (comp (ref "P199")
      (value "1,6/0,9")
      (footprint "eagle-import:1,6_0,9")
      (libsource (lib "eagle-import") (part "1,6/0,9"))
    )
    (comp (ref "P200")
      (value "1,6/0,9")
      (footprint "eagle-import:1,6_0,9")
      (libsource (lib "eagle-import") (part "1,6/0,9"))
    )
    (comp (ref "P201")
      (value "1,6/0,9")
      (footprint "eagle-import:1,6_0,9")
      (libsource (lib "eagle-import") (part "1,6/0,9"))
    )
    (comp (ref "P202")
      (value "1,6/0,9")
      (footprint "eagle-import:1,6_0,9")
      (libsource (lib "eagle-import") (part "1,6/0,9"))
    )
    (comp (ref "P203")
      (value "1,6/0,9")
      (footprint "eagle-import:1,6_0,9")
      (libsource (lib "eagle-import") (part "1,6/0,9"))
    )
    (comp (ref "P204")
      (value "1,6/0,9")
      (footprint "eagle-import:1,6_0,9")
      (libsource (lib "eagle-import") (part "1,6/0,9"))
    )
    (comp (ref "P205")
      (value "1,6/0,9")
      (footprint "eagle-import:1,6_0,9")
      (libsource (lib "eagle-import") (part "1,6/0,9"))
    )
    (comp (ref "P206")
      (value "1,6/0,9")
      (footprint "eagle-import:1,6_0,9")
      (libsource (lib "eagle-import") (part "1,6/0,9"))
    )
    (comp (ref "P207")
      (value "1,6/0,9")
      (footprint "eagle-import:1,6_0,9")
      (libsource (lib "eagle-import") (part "1,6/0,9"))
    )
    (comp (ref "P208")
      (value "1,6/0,9")
      (footprint "eagle-import:1,6_0,9")
      (libsource (lib "eagle-import") (part "1,6/0,9"))
    )
    (comp (ref "P211")
      (value "1,6/0,9")
      (footprint "eagle-import:1,6_0,9")
      (libsource (lib "eagle-import") (part "1,6/0,9"))
    )
    (comp (ref "P212")
      (value "1,6/0,9")
      (footprint "eagle-import:1,6_0,9")
      (libsource (lib "eagle-import") (part "1,6/0,9"))
    )
    (comp (ref "P213")
      (value "1,6/0,9")
      (footprint "eagle-import:1,6_0,9")
      (libsource (lib "eagle-import") (part "1,6/0,9"))
    )
    (comp (ref "P214")
      (value "1,6/0,9")
      (footprint "eagle-import:1,6_0,9")
      (libsource (lib "eagle-import") (part "1,6/0,9"))
    )
    (comp (ref "P215")
      (value "1,6/0,9")
      (footprint "eagle-import:1,6_0,9")
      (libsource (lib "eagle-import") (part "1,6/0,9"))
    )
    (comp (ref "P216")
      (value "1,6/0,9")
      (footprint "eagle-import:1,6_0,9")
      (libsource (lib "eagle-import") (part "1,6/0,9"))
    )
    (comp (ref "P217")
      (value "1,6/0,9")
      (footprint "eagle-import:1,6_0,9")
      (libsource (lib "eagle-import") (part "1,6/0,9"))
    )
    (comp (ref "P218")
      (value "1,6/0,9")
      (footprint "eagle-import:1,6_0,9")
      (libsource (lib "eagle-import") (part "1,6/0,9"))
    )
    (comp (ref "P219")
      (value "1,6/0,9")
      (footprint "eagle-import:1,6_0,9")
      (libsource (lib "eagle-import") (part "1,6/0,9"))
    )
    (comp (ref "P220")
      (value "1,6/0,9")
      (footprint "eagle-import:1,6_0,9")
      (libsource (lib "eagle-import") (part "1,6/0,9"))
    )
    (comp (ref "P221")
      (value "1,6/0,9")
      (footprint "eagle-import:1,6_0,9")
      (libsource (lib "eagle-import") (part "1,6/0,9"))
    )
    (comp (ref "P222")
      (value "1,6/0,9")
      (footprint "eagle-import:1,6_0,9")
      (libsource (lib "eagle-import") (part "1,6/0,9"))
    )
    (comp (ref "P223")
      (value "1,6/0,9")
      (footprint "eagle-import:1,6_0,9")
      (libsource (lib "eagle-import") (part "1,6/0,9"))
    )
    (comp (ref "P224")
      (value "1,6/0,9")
      (footprint "eagle-import:1,6_0,9")
      (libsource (lib "eagle-import") (part "1,6/0,9"))
    )
    (comp (ref "P225")
      (value "1,6/0,9")
      (footprint "eagle-import:1,6_0,9")
      (libsource (lib "eagle-import") (part "1,6/0,9"))
    )
    (comp (ref "P226")
      (value "1,6/0,9")
      (footprint "eagle-import:1,6_0,9")
      (libsource (lib "eagle-import") (part "1,6/0,9"))
    )
    (comp (ref "P227")
      (value "1,6/0,9")
      (footprint "eagle-import:1,6_0,9")
      (libsource (lib "eagle-import") (part "1,6/0,9"))
    )
    (comp (ref "P228")
      (value "1,6/0,9")
      (footprint "eagle-import:1,6_0,9")
      (libsource (lib "eagle-import") (part "1,6/0,9"))
    )
    (comp (ref "P229")
      (value "1,6/0,9")
      (footprint "eagle-import:1,6_0,9")
      (libsource (lib "eagle-import") (part "1,6/0,9"))
    )
    (comp (ref "P230")
      (value "1,6/0,9")
      (footprint "eagle-import:1,6_0,9")
      (libsource (lib "eagle-import") (part "1,6/0,9"))
    )
    (comp (ref "P231")
      (value "1,6/0,9")
      (footprint "eagle-import:1,6_0,9")
      (libsource (lib "eagle-import") (part "1,6/0,9"))
    )
    (comp (ref "P232")
      (value "1,6/0,9")
      (footprint "eagle-import:1,6_0,9")
      (libsource (lib "eagle-import") (part "1,6/0,9"))
    )
    (comp (ref "P233")
      (value "1,6/0,9")
      (footprint "eagle-import:1,6_0,9")
      (libsource (lib "eagle-import") (part "1,6/0,9"))
    )
    (comp (ref "P234")
      (value "1,6/0,9")
      (footprint "eagle-import:1,6_0,9")
      (libsource (lib "eagle-import") (part "1,6/0,9"))
    )
    (comp (ref "P235")
      (value "1,6/0,9")
      (footprint "eagle-import:1,6_0,9")
      (libsource (lib "eagle-import") (part "1,6/0,9"))
    )
    (comp (ref "P236")
      (value "1,6/0,9")
      (footprint "eagle-import:1,6_0,9")
      (libsource (lib "eagle-import") (part "1,6/0,9"))
    )
    (comp (ref "P237")
      (value "1,6/0,9")
      (footprint "eagle-import:1,6_0,9")
      (libsource (lib "eagle-import") (part "1,6/0,9"))
    )
    (comp (ref "P238")
      (value "1,6/0,9")
      (footprint "eagle-import:1,6_0,9")
      (libsource (lib "eagle-import") (part "1,6/0,9"))
    )
    (comp (ref "P239")
      (value "1,6/0,9")
      (footprint "eagle-import:1,6_0,9")
      (libsource (lib "eagle-import") (part "1,6/0,9"))
    )
    (comp (ref "P240")
      (value "1,6/0,9")
      (footprint "eagle-import:1,6_0,9")
      (libsource (lib "eagle-import") (part "1,6/0,9"))
    )
    (comp (ref "P241")
      (value "1,6/0,9")
      (footprint "eagle-import:1,6_0,9")
      (libsource (lib "eagle-import") (part "1,6/0,9"))
    )
    (comp (ref "P242")
      (value "1,6/0,9")
      (footprint "eagle-import:1,6_0,9")
      (libsource (lib "eagle-import") (part "1,6/0,9"))
    )
    (comp (ref "P243")
      (value "1,6/0,9")
      (footprint "eagle-import:1,6_0,9")
      (libsource (lib "eagle-import") (part "1,6/0,9"))
    )
    (comp (ref "P244")
      (value "1,6/0,9")
      (footprint "eagle-import:1,6_0,9")
      (libsource (lib "eagle-import") (part "1,6/0,9"))
    )
    (comp (ref "P245")
      (value "1,6/0,9")
      (footprint "eagle-import:1,6_0,9")
      (libsource (lib "eagle-import") (part "1,6/0,9"))
    )
    (comp (ref "P246")
      (value "1,6/0,9")
      (footprint "eagle-import:1,6_0,9")
      (libsource (lib "eagle-import") (part "1,6/0,9"))
    )
    (comp (ref "P247")
      (value "1,6/0,9")
      (footprint "eagle-import:1,6_0,9")
      (libsource (lib "eagle-import") (part "1,6/0,9"))
    )
    (comp (ref "P248")
      (value "1,6/0,9")
      (footprint "eagle-import:1,6_0,9")
      (libsource (lib "eagle-import") (part "1,6/0,9"))
    )
    (comp (ref "P249")
      (value "1,6/0,9")
      (footprint "eagle-import:1,6_0,9")
      (libsource (lib "eagle-import") (part "1,6/0,9"))
    )
    (comp (ref "P250")
      (value "1,6/0,9")
      (footprint "eagle-import:1,6_0,9")
      (libsource (lib "eagle-import") (part "1,6/0,9"))
    )
    (comp (ref "P251")
      (value "1,6/0,9")
      (footprint "eagle-import:1,6_0,9")
      (libsource (lib "eagle-import") (part "1,6/0,9"))
    )
    (comp (ref "P252")
      (value "1,6/0,9")
      (footprint "eagle-import:1,6_0,9")
      (libsource (lib "eagle-import") (part "1,6/0,9"))
    )
    (comp (ref "P253")
      (value "1,6/0,9")
      (footprint "eagle-import:1,6_0,9")
      (libsource (lib "eagle-import") (part "1,6/0,9"))
    )
    (comp (ref "P254")
      (value "1,6/0,9")
      (footprint "eagle-import:1,6_0,9")
      (libsource (lib "eagle-import") (part "1,6/0,9"))
    )
    (comp (ref "P255")
      (value "1,6/0,9")
      (footprint "eagle-import:1,6_0,9")
      (libsource (lib "eagle-import") (part "1,6/0,9"))
    )
    (comp (ref "P256")
      (value "1,6/0,9")
      (footprint "eagle-import:1,6_0,9")
      (libsource (lib "eagle-import") (part "1,6/0,9"))
    )
    (comp (ref "P257")
      (value "1,6/0,9")
      (footprint "eagle-import:1,6_0,9")
      (libsource (lib "eagle-import") (part "1,6/0,9"))
    )
    (comp (ref "P258")
      (value "1,6/0,9")
      (footprint "eagle-import:1,6_0,9")
      (libsource (lib "eagle-import") (part "1,6/0,9"))
    )
    (comp (ref "P259")
      (value "1,6/0,9")
      (footprint "eagle-import:1,6_0,9")
      (libsource (lib "eagle-import") (part "1,6/0,9"))
    )
    (comp (ref "P260")
      (value "1,6/0,9")
      (footprint "eagle-import:1,6_0,9")
      (libsource (lib "eagle-import") (part "1,6/0,9"))
    )
    (comp (ref "P261")
      (value "1,6/0,9")
      (footprint "eagle-import:1,6_0,9")
      (libsource (lib "eagle-import") (part "1,6/0,9"))
    )
    (comp (ref "P262")
      (value "1,6/0,9")
      (footprint "eagle-import:1,6_0,9")
      (libsource (lib "eagle-import") (part "1,6/0,9"))
    )
    (comp (ref "P263")
      (value "1,6/0,9")
      (footprint "eagle-import:1,6_0,9")
      (libsource (lib "eagle-import") (part "1,6/0,9"))
    )
    (comp (ref "P264")
      (value "1,6/0,9")
      (footprint "eagle-import:1,6_0,9")
      (libsource (lib "eagle-import") (part "1,6/0,9"))
    )
    (comp (ref "P265")
      (value "1,6/0,9")
      (footprint "eagle-import:1,6_0,9")
      (libsource (lib "eagle-import") (part "1,6/0,9"))
    )
    (comp (ref "P266")
      (value "1,6/0,9")
      (footprint "eagle-import:1,6_0,9")
      (libsource (lib "eagle-import") (part "1,6/0,9"))
    )
    (comp (ref "P267")
      (value "1,6/0,9")
      (footprint "eagle-import:1,6_0,9")
      (libsource (lib "eagle-import") (part "1,6/0,9"))
    )
    (comp (ref "P268")
      (value "1,6/0,9")
      (footprint "eagle-import:1,6_0,9")
      (libsource (lib "eagle-import") (part "1,6/0,9"))
    )
    (comp (ref "P269")
      (value "1,6/0,9")
      (footprint "eagle-import:1,6_0,9")
      (libsource (lib "eagle-import") (part "1,6/0,9"))
    )
    (comp (ref "P270")
      (value "1,6/0,9")
      (footprint "eagle-import:1,6_0,9")
      (libsource (lib "eagle-import") (part "1,6/0,9"))
    )
    (comp (ref "P271")
      (value "1,6/0,9")
      (footprint "eagle-import:1,6_0,9")
      (libsource (lib "eagle-import") (part "1,6/0,9"))
    )
    (comp (ref "P272")
      (value "1,6/0,9")
      (footprint "eagle-import:1,6_0,9")
      (libsource (lib "eagle-import") (part "1,6/0,9"))
    )
    (comp (ref "P273")
      (value "1,6/0,9")
      (footprint "eagle-import:1,6_0,9")
      (libsource (lib "eagle-import") (part "1,6/0,9"))
    )
    (comp (ref "P274")
      (value "1,6/0,9")
      (footprint "eagle-import:1,6_0,9")
      (libsource (lib "eagle-import") (part "1,6/0,9"))
    )
    (comp (ref "P275")
      (value "1,6/0,9")
      (footprint "eagle-import:1,6_0,9")
      (libsource (lib "eagle-import") (part "1,6/0,9"))
    )
    (comp (ref "P276")
      (value "1,6/0,9")
      (footprint "eagle-import:1,6_0,9")
      (libsource (lib "eagle-import") (part "1,6/0,9"))
    )
    (comp (ref "P277")
      (value "1,6/0,9")
      (footprint "eagle-import:1,6_0,9")
      (libsource (lib "eagle-import") (part "1,6/0,9"))
    )
    (comp (ref "P278")
      (value "1,6/0,9")
      (footprint "eagle-import:1,6_0,9")
      (libsource (lib "eagle-import") (part "1,6/0,9"))
    )
    (comp (ref "P279")
      (value "1,6/0,9")
      (footprint "eagle-import:1,6_0,9")
      (libsource (lib "eagle-import") (part "1,6/0,9"))
    )
    (comp (ref "P280")
      (value "1,6/0,9")
      (footprint "eagle-import:1,6_0,9")
      (libsource (lib "eagle-import") (part "1,6/0,9"))
    )
    (comp (ref "P281")
      (value "1,6/0,9")
      (footprint "eagle-import:1,6_0,9")
      (libsource (lib "eagle-import") (part "1,6/0,9"))
    )
    (comp (ref "P282")
      (value "1,6/0,9")
      (footprint "eagle-import:1,6_0,9")
      (libsource (lib "eagle-import") (part "1,6/0,9"))
    )
    (comp (ref "P283")
      (value "1,6/0,9")
      (footprint "eagle-import:1,6_0,9")
      (libsource (lib "eagle-import") (part "1,6/0,9"))
    )
    (comp (ref "P284")
      (value "1,6/0,9")
      (footprint "eagle-import:1,6_0,9")
      (libsource (lib "eagle-import") (part "1,6/0,9"))
    )
    (comp (ref "P285")
      (value "1,6/0,9")
      (footprint "eagle-import:1,6_0,9")
      (libsource (lib "eagle-import") (part "1,6/0,9"))
    )
    (comp (ref "P286")
      (value "1,6/0,9")
      (footprint "eagle-import:1,6_0,9")
      (libsource (lib "eagle-import") (part "1,6/0,9"))
    )
    (comp (ref "P287")
      (value "1,6/0,9")
      (footprint "eagle-import:1,6_0,9")
      (libsource (lib "eagle-import") (part "1,6/0,9"))
    )
    (comp (ref "P288")
      (value "1,6/0,9")
      (footprint "eagle-import:1,6_0,9")
      (libsource (lib "eagle-import") (part "1,6/0,9"))
    )
    (comp (ref "P289")
      (value "1,6/0,9")
      (footprint "eagle-import:1,6_0,9")
      (libsource (lib "eagle-import") (part "1,6/0,9"))
    )
    (comp (ref "P290")
      (value "1,6/0,9")
      (footprint "eagle-import:1,6_0,9")
      (libsource (lib "eagle-import") (part "1,6/0,9"))
    )
    (comp (ref "P291")
      (value "1,6/0,9")
      (footprint "eagle-import:1,6_0,9")
      (libsource (lib "eagle-import") (part "1,6/0,9"))
    )
    (comp (ref "P292")
      (value "1,6/0,9")
      (footprint "eagle-import:1,6_0,9")
      (libsource (lib "eagle-import") (part "1,6/0,9"))
    )
    (comp (ref "P293")
      (value "1,6/0,9")
      (footprint "eagle-import:1,6_0,9")
      (libsource (lib "eagle-import") (part "1,6/0,9"))
    )
    (comp (ref "P294")
      (value "1,6/0,9")
      (footprint "eagle-import:1,6_0,9")
      (libsource (lib "eagle-import") (part "1,6/0,9"))
    )
    (comp (ref "P295")
      (value "1,6/0,9")
      (footprint "eagle-import:1,6_0,9")
      (libsource (lib "eagle-import") (part "1,6/0,9"))
    )
    (comp (ref "P296")
      (value "1,6/0,9")
      (footprint "eagle-import:1,6_0,9")
      (libsource (lib "eagle-import") (part "1,6/0,9"))
    )
    (comp (ref "P297")
      (value "1,6/0,9")
      (footprint "eagle-import:1,6_0,9")
      (libsource (lib "eagle-import") (part "1,6/0,9"))
    )
    (comp (ref "P298")
      (value "1,6/0,9")
      (footprint "eagle-import:1,6_0,9")
      (libsource (lib "eagle-import") (part "1,6/0,9"))
    )
    (comp (ref "P299")
      (value "1,6/0,9")
      (footprint "eagle-import:1,6_0,9")
      (libsource (lib "eagle-import") (part "1,6/0,9"))
    )
    (comp (ref "P300")
      (value "1,6/0,9")
      (footprint "eagle-import:1,6_0,9")
      (libsource (lib "eagle-import") (part "1,6/0,9"))
    )
    (comp (ref "P301")
      (value "1,6/0,9")
      (footprint "eagle-import:1,6_0,9")
      (libsource (lib "eagle-import") (part "1,6/0,9"))
    )
    (comp (ref "P302")
      (value "1,6/0,9")
      (footprint "eagle-import:1,6_0,9")
      (libsource (lib "eagle-import") (part "1,6/0,9"))
    )
    (comp (ref "P303")
      (value "1,6/0,9")
      (footprint "eagle-import:1,6_0,9")
      (libsource (lib "eagle-import") (part "1,6/0,9"))
    )
    (comp (ref "P304")
      (value "1,6/0,9")
      (footprint "eagle-import:1,6_0,9")
      (libsource (lib "eagle-import") (part "1,6/0,9"))
    )
    (comp (ref "P305")
      (value "1,6/0,9")
      (footprint "eagle-import:1,6_0,9")
      (libsource (lib "eagle-import") (part "1,6/0,9"))
    )
    (comp (ref "P306")
      (value "1,6/0,9")
      (footprint "eagle-import:1,6_0,9")
      (libsource (lib "eagle-import") (part "1,6/0,9"))
    )
    (comp (ref "P307")
      (value "1,6/0,9")
      (footprint "eagle-import:1,6_0,9")
      (libsource (lib "eagle-import") (part "1,6/0,9"))
    )
    (comp (ref "P308")
      (value "1,6/0,9")
      (footprint "eagle-import:1,6_0,9")
      (libsource (lib "eagle-import") (part "1,6/0,9"))
    )
    (comp (ref "P309")
      (value "1,6/0,9")
      (footprint "eagle-import:1,6_0,9")
      (libsource (lib "eagle-import") (part "1,6/0,9"))
    )
    (comp (ref "P310")
      (value "1,6/0,9")
      (footprint "eagle-import:1,6_0,9")
      (libsource (lib "eagle-import") (part "1,6/0,9"))
    )
    (comp (ref "P311")
      (value "1,6/0,9")
      (footprint "eagle-import:1,6_0,9")
      (libsource (lib "eagle-import") (part "1,6/0,9"))
    )
    (comp (ref "P312")
      (value "1,6/0,9")
      (footprint "eagle-import:1,6_0,9")
      (libsource (lib "eagle-import") (part "1,6/0,9"))
    )
    (comp (ref "P313")
      (value "1,6/0,9")
      (footprint "eagle-import:1,6_0,9")
      (libsource (lib "eagle-import") (part "1,6/0,9"))
    )
    (comp (ref "P314")
      (value "1,6/0,9")
      (footprint "eagle-import:1,6_0,9")
      (libsource (lib "eagle-import") (part "1,6/0,9"))
    )
    (comp (ref "P315")
      (value "1,6/0,9")
      (footprint "eagle-import:1,6_0,9")
      (libsource (lib "eagle-import") (part "1,6/0,9"))
    )
    (comp (ref "P316")
      (value "1,6/0,9")
      (footprint "eagle-import:1,6_0,9")
      (libsource (lib "eagle-import") (part "1,6/0,9"))
    )
    (comp (ref "P317")
      (value "1,6/0,9")
      (footprint "eagle-import:1,6_0,9")
      (libsource (lib "eagle-import") (part "1,6/0,9"))
    )
    (comp (ref "P318")
      (value "1,6/0,9")
      (footprint "eagle-import:1,6_0,9")
      (libsource (lib "eagle-import") (part "1,6/0,9"))
    )
    (comp (ref "P319")
      (value "1,6/0,9")
      (footprint "eagle-import:1,6_0,9")
      (libsource (lib "eagle-import") (part "1,6/0,9"))
    )
    (comp (ref "P320")
      (value "1,6/0,9")
      (footprint "eagle-import:1,6_0,9")
      (libsource (lib "eagle-import") (part "1,6/0,9"))
    )
    (comp (ref "P321")
      (value "1,6/0,9")
      (footprint "eagle-import:1,6_0,9")
      (libsource (lib "eagle-import") (part "1,6/0,9"))
    )
    (comp (ref "P322")
      (value "1,6/0,9")
      (footprint "eagle-import:1,6_0,9")
      (libsource (lib "eagle-import") (part "1,6/0,9"))
    )
    (comp (ref "P323")
      (value "1,6/0,9")
      (footprint "eagle-import:1,6_0,9")
      (libsource (lib "eagle-import") (part "1,6/0,9"))
    )
    (comp (ref "P324")
      (value "1,6/0,9")
      (footprint "eagle-import:1,6_0,9")
      (libsource (lib "eagle-import") (part "1,6/0,9"))
    )
    (comp (ref "P325")
      (value "1,6/0,9")
      (footprint "eagle-import:1,6_0,9")
      (libsource (lib "eagle-import") (part "1,6/0,9"))
    )
    (comp (ref "P326")
      (value "1,6/0,9")
      (footprint "eagle-import:1,6_0,9")
      (libsource (lib "eagle-import") (part "1,6/0,9"))
    )
    (comp (ref "P327")
      (value "1,6/0,9")
      (footprint "eagle-import:1,6_0,9")
      (libsource (lib "eagle-import") (part "1,6/0,9"))
    )
    (comp (ref "P328")
      (value "1,6/0,9")
      (footprint "eagle-import:1,6_0,9")
      (libsource (lib "eagle-import") (part "1,6/0,9"))
    )
    (comp (ref "P329")
      (value "1,6/0,9")
      (footprint "eagle-import:1,6_0,9")
      (libsource (lib "eagle-import") (part "1,6/0,9"))
    )
    (comp (ref "P330")
      (value "1,6/0,9")
      (footprint "eagle-import:1,6_0,9")
      (libsource (lib "eagle-import") (part "1,6/0,9"))
    )
    (comp (ref "P331")
      (value "1,6/0,9")
      (footprint "eagle-import:1,6_0,9")
      (libsource (lib "eagle-import") (part "1,6/0,9"))
    )
    (comp (ref "P332")
      (value "1,6/0,9")
      (footprint "eagle-import:1,6_0,9")
      (libsource (lib "eagle-import") (part "1,6/0,9"))
    )
    (comp (ref "P333")
      (value "1,6/0,9")
      (footprint "eagle-import:1,6_0,9")
      (libsource (lib "eagle-import") (part "1,6/0,9"))
    )
    (comp (ref "P334")
      (value "1,6/0,9")
      (footprint "eagle-import:1,6_0,9")
      (libsource (lib "eagle-import") (part "1,6/0,9"))
    )
    (comp (ref "P335")
      (value "1,6/0,9")
      (footprint "eagle-import:1,6_0,9")
      (libsource (lib "eagle-import") (part "1,6/0,9"))
    )
    (comp (ref "P336")
      (value "1,6/0,9")
      (footprint "eagle-import:1,6_0,9")
      (libsource (lib "eagle-import") (part "1,6/0,9"))
    )
    (comp (ref "P337")
      (value "1,6/0,9")
      (footprint "eagle-import:1,6_0,9")
      (libsource (lib "eagle-import") (part "1,6/0,9"))
    )
    (comp (ref "P338")
      (value "1,6/0,9")
      (footprint "eagle-import:1,6_0,9")
      (libsource (lib "eagle-import") (part "1,6/0,9"))
    )
    (comp (ref "P339")
      (value "1,6/0,9")
      (footprint "eagle-import:1,6_0,9")
      (libsource (lib "eagle-import") (part "1,6/0,9"))
    )
    (comp (ref "P340")
      (value "1,6/0,9")
      (footprint "eagle-import:1,6_0,9")
      (libsource (lib "eagle-import") (part "1,6/0,9"))
    )
    (comp (ref "P341")
      (value "1,6/0,9")
      (footprint "eagle-import:1,6_0,9")
      (libsource (lib "eagle-import") (part "1,6/0,9"))
    )
    (comp (ref "P342")
      (value "1,6/0,9")
      (footprint "eagle-import:1,6_0,9")
      (libsource (lib "eagle-import") (part "1,6/0,9"))
    )
    (comp (ref "P343")
      (value "1,6/0,9")
      (footprint "eagle-import:1,6_0,9")
      (libsource (lib "eagle-import") (part "1,6/0,9"))
    )
    (comp (ref "P344")
      (value "1,6/0,9")
      (footprint "eagle-import:1,6_0,9")
      (libsource (lib "eagle-import") (part "1,6/0,9"))
    )
    (comp (ref "P345")
      (value "1,6/0,9")
      (footprint "eagle-import:1,6_0,9")
      (libsource (lib "eagle-import") (part "1,6/0,9"))
    )
    (comp (ref "P346")
      (value "1,6/0,9")
      (footprint "eagle-import:1,6_0,9")
      (libsource (lib "eagle-import") (part "1,6/0,9"))
    )
    (comp (ref "P347")
      (value "1,6/0,9")
      (footprint "eagle-import:1,6_0,9")
      (libsource (lib "eagle-import") (part "1,6/0,9"))
    )
    (comp (ref "P348")
      (value "1,6/0,9")
      (footprint "eagle-import:1,6_0,9")
      (libsource (lib "eagle-import") (part "1,6/0,9"))
    )
    (comp (ref "P349")
      (value "1,6/0,9")
      (footprint "eagle-import:1,6_0,9")
      (libsource (lib "eagle-import") (part "1,6/0,9"))
    )
    (comp (ref "P350")
      (value "1,6/0,9")
      (footprint "eagle-import:1,6_0,9")
      (libsource (lib "eagle-import") (part "1,6/0,9"))
    )
    (comp (ref "P351")
      (value "1,6/0,9")
      (footprint "eagle-import:1,6_0,9")
      (libsource (lib "eagle-import") (part "1,6/0,9"))
    )
    (comp (ref "P352")
      (value "1,6/0,9")
      (footprint "eagle-import:1,6_0,9")
      (libsource (lib "eagle-import") (part "1,6/0,9"))
    )
    (comp (ref "P353")
      (value "1,6/0,9")
      (footprint "eagle-import:1,6_0,9")
      (libsource (lib "eagle-import") (part "1,6/0,9"))
    )
    (comp (ref "P354")
      (value "1,6/0,9")
      (footprint "eagle-import:1,6_0,9")
      (libsource (lib "eagle-import") (part "1,6/0,9"))
    )
    (comp (ref "P355")
      (value "1,6/0,9")
      (footprint "eagle-import:1,6_0,9")
      (libsource (lib "eagle-import") (part "1,6/0,9"))
    )
    (comp (ref "P356")
      (value "1,6/0,9")
      (footprint "eagle-import:1,6_0,9")
      (libsource (lib "eagle-import") (part "1,6/0,9"))
    )
    (comp (ref "P357")
      (value "1,6/0,9")
      (footprint "eagle-import:1,6_0,9")
      (libsource (lib "eagle-import") (part "1,6/0,9"))
    )
    (comp (ref "P358")
      (value "1,6/0,9")
      (footprint "eagle-import:1,6_0,9")
      (libsource (lib "eagle-import") (part "1,6/0,9"))
    )
    (comp (ref "P359")
      (value "1,6/0,9")
      (footprint "eagle-import:1,6_0,9")
      (libsource (lib "eagle-import") (part "1,6/0,9"))
    )
    (comp (ref "P360")
      (value "1,6/0,9")
      (footprint "eagle-import:1,6_0,9")
      (libsource (lib "eagle-import") (part "1,6/0,9"))
    )
    (comp (ref "P361")
      (value "1,6/0,9")
      (footprint "eagle-import:1,6_0,9")
      (libsource (lib "eagle-import") (part "1,6/0,9"))
    )
    (comp (ref "P362")
      (value "1,6/0,9")
      (footprint "eagle-import:1,6_0,9")
      (libsource (lib "eagle-import") (part "1,6/0,9"))
    )
    (comp (ref "P363")
      (value "1,6/0,9")
      (footprint "eagle-import:1,6_0,9")
      (libsource (lib "eagle-import") (part "1,6/0,9"))
    )
    (comp (ref "P364")
      (value "1,6/0,9")
      (footprint "eagle-import:1,6_0,9")
      (libsource (lib "eagle-import") (part "1,6/0,9"))
    )
    (comp (ref "P365")
      (value "1,6/0,9")
      (footprint "eagle-import:1,6_0,9")
      (libsource (lib "eagle-import") (part "1,6/0,9"))
    )
    (comp (ref "P366")
      (value "1,6/0,9")
      (footprint "eagle-import:1,6_0,9")
      (libsource (lib "eagle-import") (part "1,6/0,9"))
    )
    (comp (ref "P367")
      (value "1,6/0,9")
      (footprint "eagle-import:1,6_0,9")
      (libsource (lib "eagle-import") (part "1,6/0,9"))
    )
    (comp (ref "P368")
      (value "1,6/0,9")
      (footprint "eagle-import:1,6_0,9")
      (libsource (lib "eagle-import") (part "1,6/0,9"))
    )
    (comp (ref "P369")
      (value "1,6/0,9")
      (footprint "eagle-import:1,6_0,9")
      (libsource (lib "eagle-import") (part "1,6/0,9"))
    )
    (comp (ref "P370")
      (value "1,6/0,9")
      (footprint "eagle-import:1,6_0,9")
      (libsource (lib "eagle-import") (part "1,6/0,9"))
    )
    (comp (ref "P371")
      (value "1,6/0,9")
      (footprint "eagle-import:1,6_0,9")
      (libsource (lib "eagle-import") (part "1,6/0,9"))
    )
    (comp (ref "P372")
      (value "1,6/0,9")
      (footprint "eagle-import:1,6_0,9")
      (libsource (lib "eagle-import") (part "1,6/0,9"))
    )
    (comp (ref "P373")
      (value "1,6/0,9")
      (footprint "eagle-import:1,6_0,9")
      (libsource (lib "eagle-import") (part "1,6/0,9"))
    )
    (comp (ref "P374")
      (value "1,6/0,9")
      (footprint "eagle-import:1,6_0,9")
      (libsource (lib "eagle-import") (part "1,6/0,9"))
    )
    (comp (ref "P375")
      (value "1,6/0,9")
      (footprint "eagle-import:1,6_0,9")
      (libsource (lib "eagle-import") (part "1,6/0,9"))
    )
    (comp (ref "P376")
      (value "1,6/0,9")
      (footprint "eagle-import:1,6_0,9")
      (libsource (lib "eagle-import") (part "1,6/0,9"))
    )
    (comp (ref "P377")
      (value "1,6/0,9")
      (footprint "eagle-import:1,6_0,9")
      (libsource (lib "eagle-import") (part "1,6/0,9"))
    )
    (comp (ref "P378")
      (value "1,6/0,9")
      (footprint "eagle-import:1,6_0,9")
      (libsource (lib "eagle-import") (part "1,6/0,9"))
    )
    (comp (ref "P379")
      (value "1,6/0,9")
      (footprint "eagle-import:1,6_0,9")
      (libsource (lib "eagle-import") (part "1,6/0,9"))
    )
    (comp (ref "P380")
      (value "1,6/0,9")
      (footprint "eagle-import:1,6_0,9")
      (libsource (lib "eagle-import") (part "1,6/0,9"))
    )
    (comp (ref "P381")
      (value "1,6/0,9")
      (footprint "eagle-import:1,6_0,9")
      (libsource (lib "eagle-import") (part "1,6/0,9"))
    )
    (comp (ref "P382")
      (value "1,6/0,9")
      (footprint "eagle-import:1,6_0,9")
      (libsource (lib "eagle-import") (part "1,6/0,9"))
    )
    (comp (ref "P383")
      (value "1,6/0,9")
      (footprint "eagle-import:1,6_0,9")
      (libsource (lib "eagle-import") (part "1,6/0,9"))
    )
    (comp (ref "P384")
      (value "1,6/0,9")
      (footprint "eagle-import:1,6_0,9")
      (libsource (lib "eagle-import") (part "1,6/0,9"))
    )
    (comp (ref "P385")
      (value "1,6/0,9")
      (footprint "eagle-import:1,6_0,9")
      (libsource (lib "eagle-import") (part "1,6/0,9"))
    )
    (comp (ref "P386")
      (value "1,6/0,9")
      (footprint "eagle-import:1,6_0,9")
      (libsource (lib "eagle-import") (part "1,6/0,9"))
    )
    (comp (ref "P387")
      (value "1,6/0,9")
      (footprint "eagle-import:1,6_0,9")
      (libsource (lib "eagle-import") (part "1,6/0,9"))
    )
    (comp (ref "P388")
      (value "1,6/0,9")
      (footprint "eagle-import:1,6_0,9")
      (libsource (lib "eagle-import") (part "1,6/0,9"))
    )
    (comp (ref "P389")
      (value "1,6/0,9")
      (footprint "eagle-import:1,6_0,9")
      (libsource (lib "eagle-import") (part "1,6/0,9"))
    )
    (comp (ref "P390")
      (value "1,6/0,9")
      (footprint "eagle-import:1,6_0,9")
      (libsource (lib "eagle-import") (part "1,6/0,9"))
    )
    (comp (ref "P391")
      (value "1,6/0,9")
      (footprint "eagle-import:1,6_0,9")
      (libsource (lib "eagle-import") (part "1,6/0,9"))
    )
    (comp (ref "P392")
      (value "1,6/0,9")
      (footprint "eagle-import:1,6_0,9")
      (libsource (lib "eagle-import") (part "1,6/0,9"))
    )
    (comp (ref "P393")
      (value "1,6/0,9")
      (footprint "eagle-import:1,6_0,9")
      (libsource (lib "eagle-import") (part "1,6/0,9"))
    )
    (comp (ref "P394")
      (value "1,6/0,9")
      (footprint "eagle-import:1,6_0,9")
      (libsource (lib "eagle-import") (part "1,6/0,9"))
    )
    (comp (ref "P395")
      (value "1,6/0,9")
      (footprint "eagle-import:1,6_0,9")
      (libsource (lib "eagle-import") (part "1,6/0,9"))
    )
    (comp (ref "P396")
      (value "1,6/0,9")
      (footprint "eagle-import:1,6_0,9")
      (libsource (lib "eagle-import") (part "1,6/0,9"))
    )
    (comp (ref "P397")
      (value "1,6/0,9")
      (footprint "eagle-import:1,6_0,9")
      (libsource (lib "eagle-import") (part "1,6/0,9"))
    )
    (comp (ref "P398")
      (value "1,6/0,9")
      (footprint "eagle-import:1,6_0,9")
      (libsource (lib "eagle-import") (part "1,6/0,9"))
    )
    (comp (ref "P399")
      (value "1,6/0,9")
      (footprint "eagle-import:1,6_0,9")
      (libsource (lib "eagle-import") (part "1,6/0,9"))
    )
    (comp (ref "P400")
      (value "1,6/0,9")
      (footprint "eagle-import:1,6_0,9")
      (libsource (lib "eagle-import") (part "1,6/0,9"))
    )
    (comp (ref "P401")
      (value "1,6/0,9")
      (footprint "eagle-import:1,6_0,9")
      (libsource (lib "eagle-import") (part "1,6/0,9"))
    )
    (comp (ref "P402")
      (value "1,6/0,9")
      (footprint "eagle-import:1,6_0,9")
      (libsource (lib "eagle-import") (part "1,6/0,9"))
    )
    (comp (ref "P403")
      (value "1,6/0,9")
      (footprint "eagle-import:1,6_0,9")
      (libsource (lib "eagle-import") (part "1,6/0,9"))
    )
    (comp (ref "P404")
      (value "1,6/0,9")
      (footprint "eagle-import:1,6_0,9")
      (libsource (lib "eagle-import") (part "1,6/0,9"))
    )
    (comp (ref "P405")
      (value "1,6/0,9")
      (footprint "eagle-import:1,6_0,9")
      (libsource (lib "eagle-import") (part "1,6/0,9"))
    )
    (comp (ref "P406")
      (value "1,6/0,9")
      (footprint "eagle-import:1,6_0,9")
      (libsource (lib "eagle-import") (part "1,6/0,9"))
    )
    (comp (ref "P407")
      (value "1,6/0,9")
      (footprint "eagle-import:1,6_0,9")
      (libsource (lib "eagle-import") (part "1,6/0,9"))
    )
    (comp (ref "P408")
      (value "1,6/0,9")
      (footprint "eagle-import:1,6_0,9")
      (libsource (lib "eagle-import") (part "1,6/0,9"))
    )
    (comp (ref "P409")
      (value "1,6/0,9")
      (footprint "eagle-import:1,6_0,9")
      (libsource (lib "eagle-import") (part "1,6/0,9"))
    )
    (comp (ref "P410")
      (value "1,6/0,9")
      (footprint "eagle-import:1,6_0,9")
      (libsource (lib "eagle-import") (part "1,6/0,9"))
    )
    (comp (ref "P411")
      (value "1,6/0,9")
      (footprint "eagle-import:1,6_0,9")
      (libsource (lib "eagle-import") (part "1,6/0,9"))
    )
    (comp (ref "P412")
      (value "1,6/0,9")
      (footprint "eagle-import:1,6_0,9")
      (libsource (lib "eagle-import") (part "1,6/0,9"))
    )
    (comp (ref "PD0-TXD")
      (value "PINHD-1X2")
      (footprint "eagle-import:1X02")
      (libsource (lib "eagle-import") (part "PINHD-1X2"))
    )
    (comp (ref "PD1-RXD")
      (value "PINHD-1X2")
      (footprint "eagle-import:1X02")
      (libsource (lib "eagle-import") (part "PINHD-1X2"))
    )
    (comp (ref "PWR")
      (value "LED5MM")
      (footprint "eagle-import:LED5MM")
      (libsource (lib "eagle-import") (part "LED5MM"))
    )
    (comp (ref "PWRIN")
      (value "PINHD-1X3")
      (footprint "eagle-import:1X03")
      (libsource (lib "eagle-import") (part "PINHD-1X3"))
    )
    (comp (ref "PWROUT")
      (value "PINHD-1X4")
      (footprint "eagle-import:1X04")
      (libsource (lib "eagle-import") (part "PINHD-1X4"))
    )
    (comp (ref "R1")
      (value "330 ohm")
      (footprint "eagle-import:0204_7")
      (libsource (lib "eagle-import") (part "R-US_0204/7"))
    )
    (comp (ref "R2")
      (value "330 ohm")
      (footprint "eagle-import:0204_7")
      (libsource (lib "eagle-import") (part "R-US_0204/7"))
    )
    (comp (ref "R3")
      (value "330 ohm")
      (footprint "eagle-import:0204_7")
      (libsource (lib "eagle-import") (part "R-US_0204/7"))
    )
    (comp (ref "R4")
      (value "10K")
      (footprint "eagle-import:0204_7")
      (libsource (lib "eagle-import") (part "R-US_0204/7"))
    )
    (comp (ref "R5")
      (value "330 ohm")
      (footprint "eagle-import:0204_7")
      (libsource (lib "eagle-import") (part "R-US_0204/7"))
    )
    (comp (ref "R6")
      (value "330 ohm")
      (footprint "eagle-import:0204_7")
      (libsource (lib "eagle-import") (part "R-US_0204/7"))
    )
    (comp (ref "R8")
      (value "10K")
      (footprint "eagle-import:0204_7")
      (libsource (lib "eagle-import") (part "R-US_0204/7"))
    )
    (comp (ref "R11")
      (value "10K")
      (footprint "eagle-import:0204_7")
      (libsource (lib "eagle-import") (part "R-US_0204/7"))
    )
    (comp (ref "RESET")
      (value "SWITCH-MOMENTARY-2PTH")
      (footprint "eagle-import:TACTILE-PTH")
      (libsource (lib "eagle-import") (part "SWITCH-MOMENTARY-2PTH"))
    )
    (comp (ref "RXLED")
      (value "LED5MM")
      (footprint "eagle-import:LED5MM")
      (libsource (lib "eagle-import") (part "LED5MM"))
    )
    (comp (ref "SERSTATE")
      (value "PINHD-1X6")
      (footprint "eagle-import:1X06")
      (libsource (lib "eagle-import") (part "PINHD-1X6"))
    )
    (comp (ref "SH1")
      (value "SHORT-VT5")
      (footprint "eagle-import:SHORT_TOP-50")
      (libsource (lib "eagle-import") (part "SHORT-VT5"))
    )
    (comp (ref "TXLED")
      (value "LED5MM")
      (footprint "eagle-import:LED5MM")
      (libsource (lib "eagle-import") (part "LED5MM"))
    )
    (comp (ref "U$4")
      (value "TOGGLE-CYAN-L-ZIK")
      (footprint "eagle-import:TOGGLE-CYAN-LG-ZIK")
      (libsource (lib "eagle-import") (part "TOGGLE-CYAN-L-ZIK"))
    )
    (comp (ref "U2")
      (value "FT232RLSSOP")
      (footprint "eagle-import:SSOP28DB")
      (libsource (lib "eagle-import") (part "FT232RLSSOP"))
    )
    (comp (ref "USB3->PWR")
      (value "PINHD-1X2")
      (footprint "eagle-import:1X02")
      (libsource (lib "eagle-import") (part "PINHD-1X2"))
    )
    (comp (ref "USB5->PWR")
      (value "PINHD-1X2")
      (footprint "eagle-import:1X02")
      (libsource (lib "eagle-import") (part "PINHD-1X2"))
    )
    (comp (ref "USBPORT")
      (value "PINHD-1X4")
      (footprint "eagle-import:1X04")
      (libsource (lib "eagle-import") (part "PINHD-1X4"))
    )
    (comp (ref "XTAL")
      (value "CRYSTALHC49S")
      (footprint "eagle-import:HC49_S")
      (libsource (lib "eagle-import") (part "CRYSTALHC49S"))
    )
  )
  (nets
    (net (code "1") (name "+5V") (class "Default")
      (node (ref "ALWAYS-ON") (pin "2") (pinfunction "2_2") (pintype "passive"))
      (node (ref "C3") (pin "2") (pinfunction "2_2") (pintype "passive"))
      (node (ref "IC1") (pin "5") (pinfunction "5_5") (pintype "passive"))
      (node (ref "IC1") (pin "6") (pinfunction "6_6") (pintype "passive"))
      (node (ref "IC1") (pin "7") (pinfunction "7_7") (pintype "passive"))
      (node (ref "PWROUT") (pin "3") (pinfunction "3_3") (pintype "passive"))
      (node (ref "SH1") (pin "1") (pinfunction "P$1_1") (pintype "bidirectional"))
      (node (ref "U$4") (pin "A2") (pinfunction "IOA2_A2") (pintype "bidirectional"))
    )
    (net (code "2") (name "/FTDI3") (class "Default")
      (node (ref "C1") (pin "1") (pinfunction "1_1") (pintype "passive"))
      (node (ref "U2") (pin "17") (pinfunction "3V3OUT_17") (pintype "output"))
      (node (ref "USB3->PWR") (pin "1") (pinfunction "1_1") (pintype "passive"))
    )
    (net (code "3") (name "/USB5") (class "Default")
      (node (ref "C2") (pin "1") (pinfunction "1_1") (pintype "passive"))
      (node (ref "U2") (pin "19") (pinfunction "RESET_19") (pintype "input"))
      (node (ref "U2") (pin "20") (pinfunction "VCC_20") (pintype "power_in"))
      (node (ref "U2") (pin "4") (pinfunction "VCCIO_4") (pintype "power_in"))
      (node (ref "USB5->PWR") (pin "1") (pinfunction "1_1") (pintype "passive"))
      (node (ref "USBPORT") (pin "1") (pinfunction "1_1") (pintype "passive"))
    )
    (net (code "4") (name "AREF") (class "Default")
      (node (ref "AREF-JP") (pin "1") (pinfunction "1_1") (pintype "passive"))
      (node (ref "ATMEGA") (pin "32") (pinfunction "AREF_32") (pintype "passive"))
    )
    (net (code "5") (name "AT_MISO") (class "Default")
      (node (ref "ATMEGA") (pin "7") (pinfunction "PCINT14/MISO_PB6_7") (pintype "bidirectional"))
      (node (ref "GPIO-B") (pin "7") (pinfunction "7_7") (pintype "passive"))
      (node (ref "ISP") (pin "1") (pinfunction "1_1") (pintype "passive"))
    )
    (net (code "6") (name "AT_MOSI") (class "Default")
      (node (ref "ATMEGA") (pin "6") (pinfunction "PCINT13/MOSI_PB5_6") (pintype "bidirectional"))
      (node (ref "GPIO-B") (pin "6") (pinfunction "6_6") (pintype "passive"))
      (node (ref "ISP") (pin "4") (pinfunction "4_4") (pintype "passive"))
    )
    (net (code "7") (name "AT_RESET") (class "Default")
      (node (ref "ATMEGA") (pin "9") (pinfunction "~{RESET}_9") (pintype "input"))
      (node (ref "ISP") (pin "5") (pinfunction "5_5") (pintype "passive"))
      (node (ref "R11") (pin "2") (pinfunction "2_2") (pintype "passive"))
      (node (ref "RESET") (pin "3") (pinfunction "2_3") (pintype "passive"))
    )
    (net (code "8") (name "AT_SCK") (class "Default")
      (node (ref "ATMEGA") (pin "8") (pinfunction "PCINT15/SCK_PB7_8") (pintype "bidirectional"))
      (node (ref "GPIO-B") (pin "8") (pinfunction "8_8") (pintype "passive"))
      (node (ref "ISP") (pin "3") (pinfunction "3_3") (pintype "passive"))
    )
    (net (code "9") (name "CTS") (class "Default")
      (node (ref "CTSGND") (pin "2") (pinfunction "2_2") (pintype "passive"))
      (node (ref "SERSTATE") (pin "6") (pinfunction "6_6") (pintype "passive"))
      (node (ref "U2") (pin "11") (pinfunction "CTS_11") (pintype "input"))
    )
    (net (code "10") (name "DCD") (class "Default")
      (node (ref "SERSTATE") (pin "2") (pinfunction "2_2") (pintype "passive"))
      (node (ref "U2") (pin "10") (pinfunction "DCD_10") (pintype "input"))
    )
    (net (code "11") (name "DSR") (class "Default")
      (node (ref "SERSTATE") (pin "3") (pinfunction "3_3") (pintype "passive"))
      (node (ref "U2") (pin "9") (pinfunction "DSR_9") (pintype "input"))
    )
    (net (code "12") (name "DTR") (class "Default")
      (node (ref "SERSTATE") (pin "4") (pinfunction "4_4") (pintype "passive"))
      (node (ref "U2") (pin "2") (pinfunction "DTR_2") (pintype "output"))
    )
    (net (code "13") (name "GND") (class "Default")
      (node (ref "ATMEGA") (pin "11") (pinfunction "GND_11") (pintype "power_in"))
      (node (ref "ATMEGA") (pin "31") (pinfunction "GND_31") (pintype "power_in"))
      (node (ref "BUT1") (pin "3") (pinfunction "2_3") (pintype "passive"))
      (node (ref "BUT2") (pin "3") (pinfunction "2_3") (pintype "passive"))
      (node (ref "C1") (pin "2") (pinfunction "2_2") (pintype "passive"))
      (node (ref "C2") (pin "2") (pinfunction "2_2") (pintype "passive"))
      (node (ref "C3") (pin "1") (pinfunction "1_1") (pintype "passive"))
      (node (ref "C4") (pin "2") (pinfunction "2_2") (pintype "passive"))
      (node (ref "C5") (pin "2") (pinfunction "2_2") (pintype "passive"))
      (node (ref "C6") (pin "2") (pinfunction "2_2") (pintype "passive"))
      (node (ref "C7") (pin "2") (pinfunction "2_2") (pintype "passive"))
      (node (ref "CTSGND") (pin "1") (pinfunction "1_1") (pintype "passive"))
      (node (ref "IC1") (pin "1") (pinfunction "1_1") (pintype "passive"))
      (node (ref "IC1") (pin "2") (pinfunction "2_2") (pintype "passive"))
      (node (ref "ISP") (pin "6") (pinfunction "6_6") (pintype "passive"))
      (node (ref "OPTLED1") (pin "K") (pinfunction "C_K") (pintype "passive"))
      (node (ref "OPTLED2") (pin "K") (pinfunction "C_K") (pintype "passive"))
      (node (ref "P1") (pin "1") (pinfunction "P_1") (pintype "passive"))
      (node (ref "P10") (pin "1") (pinfunction "P_1") (pintype "passive"))
      (node (ref "P11") (pin "1") (pinfunction "P_1") (pintype "passive"))
      (node (ref "P12") (pin "1") (pinfunction "P_1") (pintype "passive"))
      (node (ref "P13") (pin "1") (pinfunction "P_1") (pintype "passive"))
      (node (ref "P14") (pin "1") (pinfunction "P_1") (pintype "passive"))
      (node (ref "P15") (pin "1") (pinfunction "P_1") (pintype "passive"))
      (node (ref "P16") (pin "1") (pinfunction "P_1") (pintype "passive"))
      (node (ref "P17") (pin "1") (pinfunction "P_1") (pintype "passive"))
      (node (ref "P18") (pin "1") (pinfunction "P_1") (pintype "passive"))
      (node (ref "P183") (pin "1") (pinfunction "P_1") (pintype "passive"))
      (node (ref "P184") (pin "1") (pinfunction "P_1") (pintype "passive"))
      (node (ref "P185") (pin "1") (pinfunction "P_1") (pintype "passive"))
      (node (ref "P186") (pin "1") (pinfunction "P_1") (pintype "passive"))
      (node (ref "P187") (pin "1") (pinfunction "P_1") (pintype "passive"))
      (node (ref "P188") (pin "1") (pinfunction "P_1") (pintype "passive"))
      (node (ref "P189") (pin "1") (pinfunction "P_1") (pintype "passive"))
      (node (ref "P19") (pin "1") (pinfunction "P_1") (pintype "passive"))
      (node (ref "P190") (pin "1") (pinfunction "P_1") (pintype "passive"))
      (node (ref "P191") (pin "1") (pinfunction "P_1") (pintype "passive"))
      (node (ref "P192") (pin "1") (pinfunction "P_1") (pintype "passive"))
      (node (ref "P193") (pin "1") (pinfunction "P_1") (pintype "passive"))
      (node (ref "P194") (pin "1") (pinfunction "P_1") (pintype "passive"))
      (node (ref "P195") (pin "1") (pinfunction "P_1") (pintype "passive"))
      (node (ref "P196") (pin "1") (pinfunction "P_1") (pintype "passive"))
      (node (ref "P197") (pin "1") (pinfunction "P_1") (pintype "passive"))
      (node (ref "P198") (pin "1") (pinfunction "P_1") (pintype "passive"))
      (node (ref "P199") (pin "1") (pinfunction "P_1") (pintype "passive"))
      (node (ref "P2") (pin "1") (pinfunction "P_1") (pintype "passive"))
      (node (ref "P20") (pin "1") (pinfunction "P_1") (pintype "passive"))
      (node (ref "P200") (pin "1") (pinfunction "P_1") (pintype "passive"))
      (node (ref "P201") (pin "1") (pinfunction "P_1") (pintype "passive"))
      (node (ref "P202") (pin "1") (pinfunction "P_1") (pintype "passive"))
      (node (ref "P203") (pin "1") (pinfunction "P_1") (pintype "passive"))
      (node (ref "P204") (pin "1") (pinfunction "P_1") (pintype "passive"))
      (node (ref "P205") (pin "1") (pinfunction "P_1") (pintype "passive"))
      (node (ref "P206") (pin "1") (pinfunction "P_1") (pintype "passive"))
      (node (ref "P207") (pin "1") (pinfunction "P_1") (pintype "passive"))
      (node (ref "P208") (pin "1") (pinfunction "P_1") (pintype "passive"))
      (node (ref "P21") (pin "1") (pinfunction "P_1") (pintype "passive"))
      (node (ref "P22") (pin "1") (pinfunction "P_1") (pintype "passive"))
      (node (ref "P23") (pin "1") (pinfunction "P_1") (pintype "passive"))
      (node (ref "P24") (pin "1") (pinfunction "P_1") (pintype "passive"))
      (node (ref "P25") (pin "1") (pinfunction "P_1") (pintype "passive"))
      (node (ref "P26") (pin "1") (pinfunction "P_1") (pintype "passive"))
      (node (ref "P27") (pin "1") (pinfunction "P_1") (pintype "passive"))
      (node (ref "P28") (pin "1") (pinfunction "P_1") (pintype "passive"))
      (node (ref "P29") (pin "1") (pinfunction "P_1") (pintype "passive"))
      (node (ref "P3") (pin "1") (pinfunction "P_1") (pintype "passive"))
      (node (ref "P30") (pin "1") (pinfunction "P_1") (pintype "passive"))
      (node (ref "P31") (pin "1") (pinfunction "P_1") (pintype "passive"))
      (node (ref "P32") (pin "1") (pinfunction "P_1") (pintype "passive"))
      (node (ref "P33") (pin "1") (pinfunction "P_1") (pintype "passive"))
      (node (ref "P34") (pin "1") (pinfunction "P_1") (pintype "passive"))
      (node (ref "P35") (pin "1") (pinfunction "P_1") (pintype "passive"))
      (node (ref "P36") (pin "1") (pinfunction "P_1") (pintype "passive"))
      (node (ref "P4") (pin "1") (pinfunction "P_1") (pintype "passive"))
      (node (ref "P5") (pin "1") (pinfunction "P_1") (pintype "passive"))
      (node (ref "P6") (pin "1") (pinfunction "P_1") (pintype "passive"))
      (node (ref "P7") (pin "1") (pinfunction "P_1") (pintype "passive"))
      (node (ref "P8") (pin "1") (pinfunction "P_1") (pintype "passive"))
      (node (ref "P9") (pin "1") (pinfunction "P_1") (pintype "passive"))
      (node (ref "PWR") (pin "K") (pinfunction "C_K") (pintype "passive"))
      (node (ref "PWRIN") (pin "3") (pinfunction "3_3") (pintype "passive"))
      (node (ref "PWROUT") (pin "4") (pinfunction "4_4") (pintype "passive"))
      (node (ref "RESET") (pin "1") (pinfunction "1_1") (pintype "passive"))
      (node (ref "RXLED") (pin "K") (pinfunction "C_K") (pintype "passive"))
      (node (ref "TXLED") (pin "K") (pinfunction "C_K") (pintype "passive"))
      (node (ref "U2") (pin "18") (pinfunction "GND18_18") (pintype "power_in"))
      (node (ref "U2") (pin "21") (pinfunction "GND21_21") (pintype "power_in"))
      (node (ref "U2") (pin "25") (pinfunction "AGND_25") (pintype "power_in"))
      (node (ref "U2") (pin "26") (pinfunction "TEST_26") (pintype "input"))
      (node (ref "U2") (pin "7") (pinfunction "GND7_7") (pintype "power_in"))
      (node (ref "USBPORT") (pin "4") (pinfunction "4_4") (pintype "passive"))
    )
    (net (code "14") (name "Net-(BUT1-Pad1)") (class "Default")
      (node (ref "BUT1") (pin "1") (pinfunction "1_1") (pintype "passive"))
      (node (ref "OPTBUT") (pin "1") (pinfunction "1_1") (pintype "passive"))
      (node (ref "R8") (pin "1") (pinfunction "1_1") (pintype "passive"))
    )
    (net (code "15") (name "Net-(BUT2-Pad1)") (class "Default")
      (node (ref "BUT2") (pin "1") (pinfunction "1_1") (pintype "passive"))
      (node (ref "OPTBUT") (pin "2") (pinfunction "2_2") (pintype "passive"))
      (node (ref "R4") (pin "1") (pinfunction "1_1") (pintype "passive"))
    )
    (net (code "16") (name "Net-(OPTLED-Pad1)") (class "Default")
      (node (ref "OPTLED") (pin "1") (pinfunction "1_1") (pintype "passive"))
      (node (ref "R5") (pin "2") (pinfunction "2_2") (pintype "passive"))
    )
    (net (code "17") (name "Net-(OPTLED-Pad2)") (class "Default")
      (node (ref "OPTLED") (pin "2") (pinfunction "2_2") (pintype "passive"))
      (node (ref "R2") (pin "2") (pinfunction "2_2") (pintype "passive"))
    )
    (net (code "18") (name "Net-(OPTLED1-PadA)") (class "Default")
      (node (ref "OPTLED1") (pin "A") (pinfunction "A_A") (pintype "passive"))
      (node (ref "R5") (pin "1") (pinfunction "1_1") (pintype "passive"))
    )
    (net (code "19") (name "Net-(OPTLED2-PadA)") (class "Default")
      (node (ref "OPTLED2") (pin "A") (pinfunction "A_A") (pintype "passive"))
      (node (ref "R2") (pin "1") (pinfunction "1_1") (pintype "passive"))
    )
    (net (code "20") (name "Net-(PWR-PadA)") (class "Default")
      (node (ref "PWR") (pin "A") (pinfunction "A_A") (pintype "passive"))
      (node (ref "R1") (pin "1") (pinfunction "1_1") (pintype "passive"))
    )
    (net (code "21") (name "Net-(R3-Pad2)") (class "Default")
      (node (ref "R3") (pin "2") (pinfunction "2_2") (pintype "passive"))
      (node (ref "RXLED") (pin "A") (pinfunction "A_A") (pintype "passive"))
    )
    (net (code "22") (name "Net-(R6-Pad2)") (class "Default")
      (node (ref "R6") (pin "2") (pinfunction "2_2") (pintype "passive"))
      (node (ref "TXLED") (pin "A") (pinfunction "A_A") (pintype "passive"))
    )
    (net (code "23") (name "Net-(U2-RXD)") (class "Default")
      (node (ref "PD1-RXD") (pin "1") (pinfunction "1_1") (pintype "passive"))
      (node (ref "U2") (pin "5") (pinfunction "RXD_5") (pintype "input"))
    )
    (net (code "24") (name "Net-(U2-RXLED)") (class "Default")
      (node (ref "R3") (pin "1") (pinfunction "1_1") (pintype "passive"))
      (node (ref "U2") (pin "22") (pinfunction "RXLED_22") (pintype "input"))
    )
    (net (code "25") (name "Net-(U2-TXD)") (class "Default")
      (node (ref "PD0-TXD") (pin "1") (pinfunction "1_1") (pintype "passive"))
      (node (ref "U2") (pin "1") (pinfunction "TXD_1") (pintype "output"))
    )
    (net (code "26") (name "Net-(U2-TXLED)") (class "Default")
      (node (ref "R6") (pin "1") (pinfunction "1_1") (pintype "passive"))
      (node (ref "U2") (pin "23") (pinfunction "TXLED_23") (pintype "input"))
    )
    (net (code "27") (name "Net-(U2-USBDM)") (class "Default")
      (node (ref "U2") (pin "16") (pinfunction "USBDM_16") (pintype "bidirectional"))
      (node (ref "USBPORT") (pin "2") (pinfunction "2_2") (pintype "passive"))
    )
    (net (code "28") (name "Net-(U2-USBDP)") (class "Default")
      (node (ref "U2") (pin "15") (pinfunction "USBDP_15") (pintype "bidirectional"))
      (node (ref "USBPORT") (pin "3") (pinfunction "3_3") (pintype "passive"))
    )
    (net (code "29") (name "PA0") (class "Default")
      (node (ref "ATMEGA") (pin "40") (pinfunction "PCINT0/ADC0_PA0_40") (pintype "bidirectional"))
      (node (ref "GPIO-A") (pin "1") (pinfunction "1_1") (pintype "passive"))
    )
    (net (code "30") (name "PA1") (class "Default")
      (node (ref "ATMEGA") (pin "39") (pinfunction "PCINT1/ADC1_PA1_39") (pintype "bidirectional"))
      (node (ref "GPIO-A") (pin "2") (pinfunction "2_2") (pintype "passive"))
    )
    (net (code "31") (name "PA2") (class "Default")
      (node (ref "ATMEGA") (pin "38") (pinfunction "PCINT2/ADC2_PA2_38") (pintype "bidirectional"))
      (node (ref "GPIO-A") (pin "3") (pinfunction "3_3") (pintype "passive"))
    )
    (net (code "32") (name "PA3") (class "Default")
      (node (ref "ATMEGA") (pin "37") (pinfunction "PCINT3/ADC3_PA3_37") (pintype "bidirectional"))
      (node (ref "GPIO-A") (pin "4") (pinfunction "4_4") (pintype "passive"))
    )
    (net (code "33") (name "PA4") (class "Default")
      (node (ref "ATMEGA") (pin "36") (pinfunction "PCINT4/ADC4_PA4_36") (pintype "bidirectional"))
      (node (ref "GPIO-A") (pin "5") (pinfunction "5_5") (pintype "passive"))
    )
    (net (code "34") (name "PA5") (class "Default")
      (node (ref "ATMEGA") (pin "35") (pinfunction "PCINT5/ADC5_PA5_35") (pintype "bidirectional"))
      (node (ref "GPIO-A") (pin "6") (pinfunction "6_6") (pintype "passive"))
    )
    (net (code "35") (name "PA6") (class "Default")
      (node (ref "ATMEGA") (pin "34") (pinfunction "PCINT6/ADC6_PA6_34") (pintype "bidirectional"))
      (node (ref "GPIO-A") (pin "7") (pinfunction "7_7") (pintype "passive"))
    )
    (net (code "36") (name "PA7") (class "Default")
      (node (ref "ATMEGA") (pin "33") (pinfunction "PCINT7/ADC7_PA7_33") (pintype "bidirectional"))
      (node (ref "GPIO-A") (pin "8") (pinfunction "8_8") (pintype "passive"))
    )
    (net (code "37") (name "PB0") (class "Default")
      (node (ref "ATMEGA") (pin "1") (pinfunction "PCINT8/XCK0/T0_PB0_1") (pintype "bidirectional"))
      (node (ref "GPIO-B") (pin "1") (pinfunction "1_1") (pintype "passive"))
    )
    (net (code "38") (name "PB1") (class "Default")
      (node (ref "ATMEGA") (pin "2") (pinfunction "PCINT9/CLKO/T1_PB1_2") (pintype "bidirectional"))
      (node (ref "GPIO-B") (pin "2") (pinfunction "2_2") (pintype "passive"))
    )
    (net (code "39") (name "PB2") (class "Default")
      (node (ref "ATMEGA") (pin "3") (pinfunction "PCINT10/INT2/AIN0_PB2_3") (pintype "bidirectional"))
      (node (ref "GPIO-B") (pin "3") (pinfunction "3_3") (pintype "passive"))
    )
    (net (code "40") (name "PB3") (class "Default")
      (node (ref "ATMEGA") (pin "4") (pinfunction "PCINT11/OC0A/AIN1_PB3_4") (pintype "bidirectional"))
      (node (ref "GPIO-B") (pin "4") (pinfunction "4_4") (pintype "passive"))
    )
    (net (code "41") (name "PB4") (class "Default")
      (node (ref "ATMEGA") (pin "5") (pinfunction "PCINT12/OC0B/SS_PB4_5") (pintype "bidirectional"))
      (node (ref "GPIO-B") (pin "5") (pinfunction "5_5") (pintype "passive"))
    )
    (net (code "42") (name "PC0") (class "Default")
      (node (ref "ATMEGA") (pin "22") (pinfunction "PCINT16/SCL_PC0_22") (pintype "bidirectional"))
      (node (ref "GPIO-C") (pin "1") (pinfunction "1_1") (pintype "passive"))
    )
    (net (code "43") (name "PC1") (class "Default")
      (node (ref "ATMEGA") (pin "23") (pinfunction "PCINT17/SDA_PC1_23") (pintype "bidirectional"))
      (node (ref "GPIO-C") (pin "2") (pinfunction "2_2") (pintype "passive"))
    )
    (net (code "44") (name "PC2") (class "Default")
      (node (ref "ATMEGA") (pin "24") (pinfunction "PCINT18/TCK_PC2_24") (pintype "bidirectional"))
      (node (ref "GPIO-C") (pin "3") (pinfunction "3_3") (pintype "passive"))
    )
    (net (code "45") (name "PC3") (class "Default")
      (node (ref "ATMEGA") (pin "25") (pinfunction "PCINT19/TMS_PC3_25") (pintype "bidirectional"))
      (node (ref "GPIO-C") (pin "4") (pinfunction "4_4") (pintype "passive"))
    )
    (net (code "46") (name "PC4") (class "Default")
      (node (ref "ATMEGA") (pin "26") (pinfunction "PCINT20/TDO_PC4_26") (pintype "bidirectional"))
      (node (ref "GPIO-C") (pin "5") (pinfunction "5_5") (pintype "passive"))
    )
    (net (code "47") (name "PC5") (class "Default")
      (node (ref "ATMEGA") (pin "27") (pinfunction "PCINT21/TDI_PC5_27") (pintype "bidirectional"))
      (node (ref "GPIO-C") (pin "6") (pinfunction "6_6") (pintype "passive"))
    )
    (net (code "48") (name "PC6") (class "Default")
      (node (ref "ATMEGA") (pin "28") (pinfunction "PCINT22/TOSC1_PC6_28") (pintype "bidirectional"))
      (node (ref "GPIO-C") (pin "7") (pinfunction "7_7") (pintype "passive"))
    )
    (net (code "49") (name "PC7") (class "Default")
      (node (ref "ATMEGA") (pin "29") (pinfunction "PCINT23/TOSC2_PC7_29") (pintype "bidirectional"))
      (node (ref "GPIO-C") (pin "8") (pinfunction "8_8") (pintype "passive"))
    )
    (net (code "50") (name "PD0") (class "Default")
      (node (ref "ATMEGA") (pin "14") (pinfunction "PCINT24/RXD0_PD0_14") (pintype "bidirectional"))
      (node (ref "GPIO-D") (pin "1") (pinfunction "1_1") (pintype "passive"))
      (node (ref "PD0-TXD") (pin "2") (pinfunction "2_2") (pintype "passive"))
    )
    (net (code "51") (name "PD1") (class "Default")
      (node (ref "ATMEGA") (pin "15") (pinfunction "PCINT25/TXD0_PD1_15") (pintype "bidirectional"))
      (node (ref "GPIO-D") (pin "2") (pinfunction "2_2") (pintype "passive"))
      (node (ref "PD1-RXD") (pin "2") (pinfunction "2_2") (pintype "passive"))
    )
    (net (code "52") (name "PD2") (class "Default")
      (node (ref "ATMEGA") (pin "16") (pinfunction "PCINT26/INT0_PD2_16") (pintype "bidirectional"))
      (node (ref "GPIO-D") (pin "3") (pinfunction "3_3") (pintype "passive"))
    )
    (net (code "53") (name "PD3") (class "Default")
      (node (ref "ATMEGA") (pin "17") (pinfunction "PCINT27/INT1_PD3_17") (pintype "bidirectional"))
      (node (ref "GPIO-D") (pin "4") (pinfunction "4_4") (pintype "passive"))
    )
    (net (code "54") (name "PD4") (class "Default")
      (node (ref "ATMEGA") (pin "18") (pinfunction "PCINT28/OC1B_PD4_18") (pintype "bidirectional"))
      (node (ref "GPIO-D") (pin "5") (pinfunction "5_5") (pintype "passive"))
    )
    (net (code "55") (name "PD5") (class "Default")
      (node (ref "ATMEGA") (pin "19") (pinfunction "PCINT29/OC1A_PD5_19") (pintype "bidirectional"))
      (node (ref "GPIO-D") (pin "6") (pinfunction "6_6") (pintype "passive"))
    )
    (net (code "56") (name "PD6") (class "Default")
      (node (ref "ATMEGA") (pin "20") (pinfunction "PCINT30/OC2B/ICP_PD6_20") (pintype "bidirectional"))
      (node (ref "GPIO-D") (pin "7") (pinfunction "7_7") (pintype "passive"))
    )
    (net (code "57") (name "PD7") (class "Default")
      (node (ref "ATMEGA") (pin "21") (pinfunction "PCINT31/OC2A_PD7_21") (pintype "bidirectional"))
      (node (ref "GPIO-D") (pin "8") (pinfunction "8_8") (pintype "passive"))
    )
    (net (code "58") (name "PWR") (class "Default")
      (node (ref "ALWAYS-ON") (pin "1") (pinfunction "1_1") (pintype "passive"))
      (node (ref "AREF-JP") (pin "2") (pinfunction "2_2") (pintype "passive"))
      (node (ref "ATMEGA") (pin "10") (pinfunction "VCC_10") (pintype "power_in"))
      (node (ref "ATMEGA") (pin "30") (pinfunction "AVCC_30") (pintype "power_in"))
      (node (ref "C4") (pin "1") (pinfunction "1_1") (pintype "passive"))
      (node (ref "C5") (pin "1") (pinfunction "1_1") (pintype "passive"))
      (node (ref "ISP") (pin "2") (pinfunction "2_2") (pintype "passive"))
      (node (ref "P108") (pin "1") (pinfunction "P_1") (pintype "passive"))
      (node (ref "P109") (pin "1") (pinfunction "P_1") (pintype "passive"))
      (node (ref "P110") (pin "1") (pinfunction "P_1") (pintype "passive"))
      (node (ref "P111") (pin "1") (pinfunction "P_1") (pintype "passive"))
      (node (ref "P112") (pin "1") (pinfunction "P_1") (pintype "passive"))
      (node (ref "P211") (pin "1") (pinfunction "P_1") (pintype "passive"))
      (node (ref "P212") (pin "1") (pinfunction "P_1") (pintype "passive"))
      (node (ref "P213") (pin "1") (pinfunction "P_1") (pintype "passive"))
      (node (ref "P214") (pin "1") (pinfunction "P_1") (pintype "passive"))
      (node (ref "P215") (pin "1") (pinfunction "P_1") (pintype "passive"))
      (node (ref "P216") (pin "1") (pinfunction "P_1") (pintype "passive"))
      (node (ref "P217") (pin "1") (pinfunction "P_1") (pintype "passive"))
      (node (ref "P218") (pin "1") (pinfunction "P_1") (pintype "passive"))
      (node (ref "P219") (pin "1") (pinfunction "P_1") (pintype "passive"))
      (node (ref "P220") (pin "1") (pinfunction "P_1") (pintype "passive"))
      (node (ref "P221") (pin "1") (pinfunction "P_1") (pintype "passive"))
      (node (ref "P222") (pin "1") (pinfunction "P_1") (pintype "passive"))
      (node (ref "P223") (pin "1") (pinfunction "P_1") (pintype "passive"))
      (node (ref "P224") (pin "1") (pinfunction "P_1") (pintype "passive"))
      (node (ref "P225") (pin "1") (pinfunction "P_1") (pintype "passive"))
      (node (ref "P226") (pin "1") (pinfunction "P_1") (pintype "passive"))
      (node (ref "P227") (pin "1") (pinfunction "P_1") (pintype "passive"))
      (node (ref "P228") (pin "1") (pinfunction "P_1") (pintype "passive"))
      (node (ref "P229") (pin "1") (pinfunction "P_1") (pintype "passive"))
      (node (ref "P230") (pin "1") (pinfunction "P_1") (pintype "passive"))
      (node (ref "P231") (pin "1") (pinfunction "P_1") (pintype "passive"))
      (node (ref "P232") (pin "1") (pinfunction "P_1") (pintype "passive"))
      (node (ref "P233") (pin "1") (pinfunction "P_1") (pintype "passive"))
      (node (ref "P234") (pin "1") (pinfunction "P_1") (pintype "passive"))
      (node (ref "P235") (pin "1") (pinfunction "P_1") (pintype "passive"))
      (node (ref "P236") (pin "1") (pinfunction "P_1") (pintype "passive"))
      (node (ref "P37") (pin "1") (pinfunction "P_1") (pintype "passive"))
      (node (ref "P38") (pin "1") (pinfunction "P_1") (pintype "passive"))
      (node (ref "P39") (pin "1") (pinfunction "P_1") (pintype "passive"))
      (node (ref "P40") (pin "1") (pinfunction "P_1") (pintype "passive"))
      (node (ref "P41") (pin "1") (pinfunction "P_1") (pintype "passive"))
      (node (ref "P62") (pin "1") (pinfunction "P_1") (pintype "passive"))
      (node (ref "P64") (pin "1") (pinfunction "P_1") (pintype "passive"))
      (node (ref "P71") (pin "1") (pinfunction "P_1") (pintype "passive"))
      (node (ref "P74") (pin "1") (pinfunction "P_1") (pintype "passive"))
      (node (ref "P78") (pin "1") (pinfunction "P_1") (pintype "passive"))
      (node (ref "P79") (pin "1") (pinfunction "P_1") (pintype "passive"))
      (node (ref "P80") (pin "1") (pinfunction "P_1") (pintype "passive"))
      (node (ref "P81") (pin "1") (pinfunction "P_1") (pintype "passive"))
      (node (ref "P82") (pin "1") (pinfunction "P_1") (pintype "passive"))
      (node (ref "P83") (pin "1") (pinfunction "P_1") (pintype "passive"))
      (node (ref "P84") (pin "1") (pinfunction "P_1") (pintype "passive"))
      (node (ref "P85") (pin "1") (pinfunction "P_1") (pintype "passive"))
      (node (ref "P86") (pin "1") (pinfunction "P_1") (pintype "passive"))
      (node (ref "P87") (pin "1") (pinfunction "P_1") (pintype "passive"))
      (node (ref "P88") (pin "1") (pinfunction "P_1") (pintype "passive"))
      (node (ref "P89") (pin "1") (pinfunction "P_1") (pintype "passive"))
      (node (ref "P90") (pin "1") (pinfunction "P_1") (pintype "passive"))
      (node (ref "P91") (pin "1") (pinfunction "P_1") (pintype "passive"))
      (node (ref "P92") (pin "1") (pinfunction "P_1") (pintype "passive"))
      (node (ref "P93") (pin "1") (pinfunction "P_1") (pintype "passive"))
      (node (ref "P94") (pin "1") (pinfunction "P_1") (pintype "passive"))
      (node (ref "P95") (pin "1") (pinfunction "P_1") (pintype "passive"))
      (node (ref "P96") (pin "1") (pinfunction "P_1") (pintype "passive"))
      (node (ref "P97") (pin "1") (pinfunction "P_1") (pintype "passive"))
      (node (ref "P98") (pin "1") (pinfunction "P_1") (pintype "passive"))
      (node (ref "P99") (pin "1") (pinfunction "P_1") (pintype "passive"))
      (node (ref "R1") (pin "2") (pinfunction "2_2") (pintype "passive"))
      (node (ref "R11") (pin "1") (pinfunction "1_1") (pintype "passive"))
      (node (ref "R4") (pin "2") (pinfunction "2_2") (pintype "passive"))
      (node (ref "R8") (pin "2") (pinfunction "2_2") (pintype "passive"))
      (node (ref "U$4") (pin "A!") (pinfunction "IOA1_A!") (pintype "bidirectional"))
      (node (ref "USB3->PWR") (pin "2") (pinfunction "2_2") (pintype "passive"))
      (node (ref "USB5->PWR") (pin "2") (pinfunction "2_2") (pintype "passive"))
    )
    (net (code "59") (name "RI") (class "Default")
      (node (ref "SERSTATE") (pin "1") (pinfunction "1_1") (pintype "passive"))
      (node (ref "U2") (pin "6") (pinfunction "RI_6") (pintype "input"))
    )
    (net (code "60") (name "RTS") (class "Default")
      (node (ref "SERSTATE") (pin "5") (pinfunction "5_5") (pintype "passive"))
      (node (ref "U2") (pin "3") (pinfunction "RTS_3") (pintype "output"))
    )
    (net (code "61") (name "V+") (class "Default")
      (node (ref "PWRIN") (pin "2") (pinfunction "2_2") (pintype "passive"))
      (node (ref "PWROUT") (pin "2") (pinfunction "2_2") (pintype "passive"))
      (node (ref "SH1") (pin "2") (pinfunction "P$2_2") (pintype "bidirectional"))
    )
    (net (code "62") (name "VCC") (class "Default")
      (node (ref "IC1") (pin "3") (pinfunction "3_3") (pintype "passive"))
      (node (ref "IC1") (pin "4") (pinfunction "4_4") (pintype "passive"))
      (node (ref "PWRIN") (pin "1") (pinfunction "1_1") (pintype "passive"))
      (node (ref "PWROUT") (pin "1") (pinfunction "1_1") (pintype "passive"))
    )
    (net (code "63") (name "XTAL1") (class "Default")
      (node (ref "ATMEGA") (pin "13") (pinfunction "XTAL1_13") (pintype "input"))
      (node (ref "C7") (pin "1") (pinfunction "1_1") (pintype "passive"))
      (node (ref "XTAL") (pin "1") (pinfunction "1_1") (pintype "passive"))
    )
    (net (code "64") (name "XTAL2") (class "Default")
      (node (ref "ATMEGA") (pin "12") (pinfunction "XTAL2_12") (pintype "output"))
      (node (ref "C6") (pin "1") (pinfunction "1_1") (pintype "passive"))
      (node (ref "XTAL") (pin "2") (pinfunction "2_2") (pintype "passive"))
    )
    (net (code "65") (name "unconnected-(IC1-Pad8)") (class "Default")
      (node (ref "IC1") (pin "8") (pinfunction "8_8") (pintype "passive"))
    )
    (net (code "66") (name "unconnected-(P42-P-Pad1)") (class "Default")
      (node (ref "P42") (pin "1") (pinfunction "P_1") (pintype "passive"))
    )
    (net (code "67") (name "unconnected-(P43-P-Pad1)") (class "Default")
      (node (ref "P43") (pin "1") (pinfunction "P_1") (pintype "passive"))
    )
    (net (code "68") (name "unconnected-(P44-P-Pad1)") (class "Default")
      (node (ref "P44") (pin "1") (pinfunction "P_1") (pintype "passive"))
    )
    (net (code "69") (name "unconnected-(P45-P-Pad1)") (class "Default")
      (node (ref "P45") (pin "1") (pinfunction "P_1") (pintype "passive"))
    )
    (net (code "70") (name "unconnected-(P46-P-Pad1)") (class "Default")
      (node (ref "P46") (pin "1") (pinfunction "P_1") (pintype "passive"))
    )
    (net (code "71") (name "unconnected-(P47-P-Pad1)") (class "Default")
      (node (ref "P47") (pin "1") (pinfunction "P_1") (pintype "passive"))
    )
    (net (code "72") (name "unconnected-(P48-P-Pad1)") (class "Default")
      (node (ref "P48") (pin "1") (pinfunction "P_1") (pintype "passive"))
    )
    (net (code "73") (name "unconnected-(P49-P-Pad1)") (class "Default")
      (node (ref "P49") (pin "1") (pinfunction "P_1") (pintype "passive"))
    )
    (net (code "74") (name "unconnected-(P50-P-Pad1)") (class "Default")
      (node (ref "P50") (pin "1") (pinfunction "P_1") (pintype "passive"))
    )
    (net (code "75") (name "unconnected-(P51-P-Pad1)") (class "Default")
      (node (ref "P51") (pin "1") (pinfunction "P_1") (pintype "passive"))
    )
    (net (code "76") (name "unconnected-(P52-P-Pad1)") (class "Default")
      (node (ref "P52") (pin "1") (pinfunction "P_1") (pintype "passive"))
    )
    (net (code "77") (name "unconnected-(P53-P-Pad1)") (class "Default")
      (node (ref "P53") (pin "1") (pinfunction "P_1") (pintype "passive"))
    )
    (net (code "78") (name "unconnected-(P54-P-Pad1)") (class "Default")
      (node (ref "P54") (pin "1") (pinfunction "P_1") (pintype "passive"))
    )
    (net (code "79") (name "unconnected-(P55-P-Pad1)") (class "Default")
      (node (ref "P55") (pin "1") (pinfunction "P_1") (pintype "passive"))
    )
    (net (code "80") (name "unconnected-(P56-P-Pad1)") (class "Default")
      (node (ref "P56") (pin "1") (pinfunction "P_1") (pintype "passive"))
    )
    (net (code "81") (name "unconnected-(P57-P-Pad1)") (class "Default")
      (node (ref "P57") (pin "1") (pinfunction "P_1") (pintype "passive"))
    )
    (net (code "82") (name "unconnected-(P58-P-Pad1)") (class "Default")
      (node (ref "P58") (pin "1") (pinfunction "P_1") (pintype "passive"))
    )
    (net (code "83") (name "unconnected-(P59-P-Pad1)") (class "Default")
      (node (ref "P59") (pin "1") (pinfunction "P_1") (pintype "passive"))
    )
    (net (code "84") (name "unconnected-(P60-P-Pad1)") (class "Default")
      (node (ref "P60") (pin "1") (pinfunction "P_1") (pintype "passive"))
    )
    (net (code "85") (name "unconnected-(P61-P-Pad1)") (class "Default")
      (node (ref "P61") (pin "1") (pinfunction "P_1") (pintype "passive"))
    )
    (net (code "86") (name "unconnected-(P63-P-Pad1)") (class "Default")
      (node (ref "P63") (pin "1") (pinfunction "P_1") (pintype "passive"))
    )
    (net (code "87") (name "unconnected-(P65-P-Pad1)") (class "Default")
      (node (ref "P65") (pin "1") (pinfunction "P_1") (pintype "passive"))
    )
    (net (code "88") (name "unconnected-(P66-P-Pad1)") (class "Default")
      (node (ref "P66") (pin "1") (pinfunction "P_1") (pintype "passive"))
    )
    (net (code "89") (name "unconnected-(P67-P-Pad1)") (class "Default")
      (node (ref "P67") (pin "1") (pinfunction "P_1") (pintype "passive"))
    )
    (net (code "90") (name "unconnected-(P68-P-Pad1)") (class "Default")
      (node (ref "P68") (pin "1") (pinfunction "P_1") (pintype "passive"))
    )
    (net (code "91") (name "unconnected-(P69-P-Pad1)") (class "Default")
      (node (ref "P69") (pin "1") (pinfunction "P_1") (pintype "passive"))
    )
    (net (code "92") (name "unconnected-(P70-P-Pad1)") (class "Default")
      (node (ref "P70") (pin "1") (pinfunction "P_1") (pintype "passive"))
    )
    (net (code "93") (name "unconnected-(P72-P-Pad1)") (class "Default")
      (node (ref "P72") (pin "1") (pinfunction "P_1") (pintype "passive"))
    )
    (net (code "94") (name "unconnected-(P73-P-Pad1)") (class "Default")
      (node (ref "P73") (pin "1") (pinfunction "P_1") (pintype "passive"))
    )
    (net (code "95") (name "unconnected-(P75-P-Pad1)") (class "Default")
      (node (ref "P75") (pin "1") (pinfunction "P_1") (pintype "passive"))
    )
    (net (code "96") (name "unconnected-(P76-P-Pad1)") (class "Default")
      (node (ref "P76") (pin "1") (pinfunction "P_1") (pintype "passive"))
    )
    (net (code "97") (name "unconnected-(P77-P-Pad1)") (class "Default")
      (node (ref "P77") (pin "1") (pinfunction "P_1") (pintype "passive"))
    )
    (net (code "98") (name "unconnected-(P100-P-Pad1)") (class "Default")
      (node (ref "P100") (pin "1") (pinfunction "P_1") (pintype "passive"))
    )
    (net (code "99") (name "unconnected-(P101-P-Pad1)") (class "Default")
      (node (ref "P101") (pin "1") (pinfunction "P_1") (pintype "passive"))
    )
    (net (code "100") (name "unconnected-(P102-P-Pad1)") (class "Default")
      (node (ref "P102") (pin "1") (pinfunction "P_1") (pintype "passive"))
    )
    (net (code "101") (name "unconnected-(P103-P-Pad1)") (class "Default")
      (node (ref "P103") (pin "1") (pinfunction "P_1") (pintype "passive"))
    )
    (net (code "102") (name "unconnected-(P104-P-Pad1)") (class "Default")
      (node (ref "P104") (pin "1") (pinfunction "P_1") (pintype "passive"))
    )
    (net (code "103") (name "unconnected-(P105-P-Pad1)") (class "Default")
      (node (ref "P105") (pin "1") (pinfunction "P_1") (pintype "passive"))
    )
    (net (code "104") (name "unconnected-(P106-P-Pad1)") (class "Default")
      (node (ref "P106") (pin "1") (pinfunction "P_1") (pintype "passive"))
    )
    (net (code "105") (name "unconnected-(P107-P-Pad1)") (class "Default")
      (node (ref "P107") (pin "1") (pinfunction "P_1") (pintype "passive"))
    )
    (net (code "106") (name "unconnected-(P113-P-Pad1)") (class "Default")
      (node (ref "P113") (pin "1") (pinfunction "P_1") (pintype "passive"))
    )
    (net (code "107") (name "unconnected-(P114-P-Pad1)") (class "Default")
      (node (ref "P114") (pin "1") (pinfunction "P_1") (pintype "passive"))
    )
    (net (code "108") (name "unconnected-(P115-P-Pad1)") (class "Default")
      (node (ref "P115") (pin "1") (pinfunction "P_1") (pintype "passive"))
    )
    (net (code "109") (name "unconnected-(P116-P-Pad1)") (class "Default")
      (node (ref "P116") (pin "1") (pinfunction "P_1") (pintype "passive"))
    )
    (net (code "110") (name "unconnected-(P117-P-Pad1)") (class "Default")
      (node (ref "P117") (pin "1") (pinfunction "P_1") (pintype "passive"))
    )
    (net (code "111") (name "unconnected-(P118-P-Pad1)") (class "Default")
      (node (ref "P118") (pin "1") (pinfunction "P_1") (pintype "passive"))
    )
    (net (code "112") (name "unconnected-(P119-P-Pad1)") (class "Default")
      (node (ref "P119") (pin "1") (pinfunction "P_1") (pintype "passive"))
    )
    (net (code "113") (name "unconnected-(P120-P-Pad1)") (class "Default")
      (node (ref "P120") (pin "1") (pinfunction "P_1") (pintype "passive"))
    )
    (net (code "114") (name "unconnected-(P121-P-Pad1)") (class "Default")
      (node (ref "P121") (pin "1") (pinfunction "P_1") (pintype "passive"))
    )
    (net (code "115") (name "unconnected-(P122-P-Pad1)") (class "Default")
      (node (ref "P122") (pin "1") (pinfunction "P_1") (pintype "passive"))
    )
    (net (code "116") (name "unconnected-(P123-P-Pad1)") (class "Default")
      (node (ref "P123") (pin "1") (pinfunction "P_1") (pintype "passive"))
    )
    (net (code "117") (name "unconnected-(P124-P-Pad1)") (class "Default")
      (node (ref "P124") (pin "1") (pinfunction "P_1") (pintype "passive"))
    )
    (net (code "118") (name "unconnected-(P125-P-Pad1)") (class "Default")
      (node (ref "P125") (pin "1") (pinfunction "P_1") (pintype "passive"))
    )
    (net (code "119") (name "unconnected-(P126-P-Pad1)") (class "Default")
      (node (ref "P126") (pin "1") (pinfunction "P_1") (pintype "passive"))
    )
    (net (code "120") (name "unconnected-(P127-P-Pad1)") (class "Default")
      (node (ref "P127") (pin "1") (pinfunction "P_1") (pintype "passive"))
    )
    (net (code "121") (name "unconnected-(P128-P-Pad1)") (class "Default")
      (node (ref "P128") (pin "1") (pinfunction "P_1") (pintype "passive"))
    )
    (net (code "122") (name "unconnected-(P129-P-Pad1)") (class "Default")
      (node (ref "P129") (pin "1") (pinfunction "P_1") (pintype "passive"))
    )
    (net (code "123") (name "unconnected-(P130-P-Pad1)") (class "Default")
      (node (ref "P130") (pin "1") (pinfunction "P_1") (pintype "passive"))
    )
    (net (code "124") (name "unconnected-(P139-P-Pad1)") (class "Default")
      (node (ref "P139") (pin "1") (pinfunction "P_1") (pintype "passive"))
    )
    (net (code "125") (name "unconnected-(P140-P-Pad1)") (class "Default")
      (node (ref "P140") (pin "1") (pinfunction "P_1") (pintype "passive"))
    )
    (net (code "126") (name "unconnected-(P141-P-Pad1)") (class "Default")
      (node (ref "P141") (pin "1") (pinfunction "P_1") (pintype "passive"))
    )
    (net (code "127") (name "unconnected-(P142-P-Pad1)") (class "Default")
      (node (ref "P142") (pin "1") (pinfunction "P_1") (pintype "passive"))
    )
    (net (code "128") (name "unconnected-(P143-P-Pad1)") (class "Default")
      (node (ref "P143") (pin "1") (pinfunction "P_1") (pintype "passive"))
    )
    (net (code "129") (name "unconnected-(P144-P-Pad1)") (class "Default")
      (node (ref "P144") (pin "1") (pinfunction "P_1") (pintype "passive"))
    )
    (net (code "130") (name "unconnected-(P145-P-Pad1)") (class "Default")
      (node (ref "P145") (pin "1") (pinfunction "P_1") (pintype "passive"))
    )
    (net (code "131") (name "unconnected-(P146-P-Pad1)") (class "Default")
      (node (ref "P146") (pin "1") (pinfunction "P_1") (pintype "passive"))
    )
    (net (code "132") (name "unconnected-(P147-P-Pad1)") (class "Default")
      (node (ref "P147") (pin "1") (pinfunction "P_1") (pintype "passive"))
    )
    (net (code "133") (name "unconnected-(P148-P-Pad1)") (class "Default")
      (node (ref "P148") (pin "1") (pinfunction "P_1") (pintype "passive"))
    )
    (net (code "134") (name "unconnected-(P149-P-Pad1)") (class "Default")
      (node (ref "P149") (pin "1") (pinfunction "P_1") (pintype "passive"))
    )
    (net (code "135") (name "unconnected-(P150-P-Pad1)") (class "Default")
      (node (ref "P150") (pin "1") (pinfunction "P_1") (pintype "passive"))
    )
    (net (code "136") (name "unconnected-(P151-P-Pad1)") (class "Default")
      (node (ref "P151") (pin "1") (pinfunction "P_1") (pintype "passive"))
    )
    (net (code "137") (name "unconnected-(P152-P-Pad1)") (class "Default")
      (node (ref "P152") (pin "1") (pinfunction "P_1") (pintype "passive"))
    )
    (net (code "138") (name "unconnected-(P153-P-Pad1)") (class "Default")
      (node (ref "P153") (pin "1") (pinfunction "P_1") (pintype "passive"))
    )
    (net (code "139") (name "unconnected-(P154-P-Pad1)") (class "Default")
      (node (ref "P154") (pin "1") (pinfunction "P_1") (pintype "passive"))
    )
    (net (code "140") (name "unconnected-(P155-P-Pad1)") (class "Default")
      (node (ref "P155") (pin "1") (pinfunction "P_1") (pintype "passive"))
    )
    (net (code "141") (name "unconnected-(P156-P-Pad1)") (class "Default")
      (node (ref "P156") (pin "1") (pinfunction "P_1") (pintype "passive"))
    )
    (net (code "142") (name "unconnected-(P157-P-Pad1)") (class "Default")
      (node (ref "P157") (pin "1") (pinfunction "P_1") (pintype "passive"))
    )
    (net (code "143") (name "unconnected-(P158-P-Pad1)") (class "Default")
      (node (ref "P158") (pin "1") (pinfunction "P_1") (pintype "passive"))
    )
    (net (code "144") (name "unconnected-(P159-P-Pad1)") (class "Default")
      (node (ref "P159") (pin "1") (pinfunction "P_1") (pintype "passive"))
    )
    (net (code "145") (name "unconnected-(P160-P-Pad1)") (class "Default")
      (node (ref "P160") (pin "1") (pinfunction "P_1") (pintype "passive"))
    )
    (net (code "146") (name "unconnected-(P161-P-Pad1)") (class "Default")
      (node (ref "P161") (pin "1") (pinfunction "P_1") (pintype "passive"))
    )
    (net (code "147") (name "unconnected-(P162-P-Pad1)") (class "Default")
      (node (ref "P162") (pin "1") (pinfunction "P_1") (pintype "passive"))
    )
    (net (code "148") (name "unconnected-(P163-P-Pad1)") (class "Default")
      (node (ref "P163") (pin "1") (pinfunction "P_1") (pintype "passive"))
    )
    (net (code "149") (name "unconnected-(P164-P-Pad1)") (class "Default")
      (node (ref "P164") (pin "1") (pinfunction "P_1") (pintype "passive"))
    )
    (net (code "150") (name "unconnected-(P165-P-Pad1)") (class "Default")
      (node (ref "P165") (pin "1") (pinfunction "P_1") (pintype "passive"))
    )
    (net (code "151") (name "unconnected-(P166-P-Pad1)") (class "Default")
      (node (ref "P166") (pin "1") (pinfunction "P_1") (pintype "passive"))
    )
    (net (code "152") (name "unconnected-(P167-P-Pad1)") (class "Default")
      (node (ref "P167") (pin "1") (pinfunction "P_1") (pintype "passive"))
    )
    (net (code "153") (name "unconnected-(P168-P-Pad1)") (class "Default")
      (node (ref "P168") (pin "1") (pinfunction "P_1") (pintype "passive"))
    )
    (net (code "154") (name "unconnected-(P169-P-Pad1)") (class "Default")
      (node (ref "P169") (pin "1") (pinfunction "P_1") (pintype "passive"))
    )
    (net (code "155") (name "unconnected-(P170-P-Pad1)") (class "Default")
      (node (ref "P170") (pin "1") (pinfunction "P_1") (pintype "passive"))
    )
    (net (code "156") (name "unconnected-(P171-P-Pad1)") (class "Default")
      (node (ref "P171") (pin "1") (pinfunction "P_1") (pintype "passive"))
    )
    (net (code "157") (name "unconnected-(P172-P-Pad1)") (class "Default")
      (node (ref "P172") (pin "1") (pinfunction "P_1") (pintype "passive"))
    )
    (net (code "158") (name "unconnected-(P173-P-Pad1)") (class "Default")
      (node (ref "P173") (pin "1") (pinfunction "P_1") (pintype "passive"))
    )
    (net (code "159") (name "unconnected-(P174-P-Pad1)") (class "Default")
      (node (ref "P174") (pin "1") (pinfunction "P_1") (pintype "passive"))
    )
    (net (code "160") (name "unconnected-(P175-P-Pad1)") (class "Default")
      (node (ref "P175") (pin "1") (pinfunction "P_1") (pintype "passive"))
    )
    (net (code "161") (name "unconnected-(P176-P-Pad1)") (class "Default")
      (node (ref "P176") (pin "1") (pinfunction "P_1") (pintype "passive"))
    )
    (net (code "162") (name "unconnected-(P177-P-Pad1)") (class "Default")
      (node (ref "P177") (pin "1") (pinfunction "P_1") (pintype "passive"))
    )
    (net (code "163") (name "unconnected-(P178-P-Pad1)") (class "Default")
      (node (ref "P178") (pin "1") (pinfunction "P_1") (pintype "passive"))
    )
    (net (code "164") (name "unconnected-(P179-P-Pad1)") (class "Default")
      (node (ref "P179") (pin "1") (pinfunction "P_1") (pintype "passive"))
    )
    (net (code "165") (name "unconnected-(P180-P-Pad1)") (class "Default")
      (node (ref "P180") (pin "1") (pinfunction "P_1") (pintype "passive"))
    )
    (net (code "166") (name "unconnected-(P237-P-Pad1)") (class "Default")
      (node (ref "P237") (pin "1") (pinfunction "P_1") (pintype "passive"))
    )
    (net (code "167") (name "unconnected-(P238-P-Pad1)") (class "Default")
      (node (ref "P238") (pin "1") (pinfunction "P_1") (pintype "passive"))
    )
    (net (code "168") (name "unconnected-(P239-P-Pad1)") (class "Default")
      (node (ref "P239") (pin "1") (pinfunction "P_1") (pintype "passive"))
    )
    (net (code "169") (name "unconnected-(P240-P-Pad1)") (class "Default")
      (node (ref "P240") (pin "1") (pinfunction "P_1") (pintype "passive"))
    )
    (net (code "170") (name "unconnected-(P241-P-Pad1)") (class "Default")
      (node (ref "P241") (pin "1") (pinfunction "P_1") (pintype "passive"))
    )
    (net (code "171") (name "unconnected-(P242-P-Pad1)") (class "Default")
      (node (ref "P242") (pin "1") (pinfunction "P_1") (pintype "passive"))
    )
    (net (code "172") (name "unconnected-(P243-P-Pad1)") (class "Default")
      (node (ref "P243") (pin "1") (pinfunction "P_1") (pintype "passive"))
    )
    (net (code "173") (name "unconnected-(P244-P-Pad1)") (class "Default")
      (node (ref "P244") (pin "1") (pinfunction "P_1") (pintype "passive"))
    )
    (net (code "174") (name "unconnected-(P245-P-Pad1)") (class "Default")
      (node (ref "P245") (pin "1") (pinfunction "P_1") (pintype "passive"))
    )
    (net (code "175") (name "unconnected-(P246-P-Pad1)") (class "Default")
      (node (ref "P246") (pin "1") (pinfunction "P_1") (pintype "passive"))
    )
    (net (code "176") (name "unconnected-(P247-P-Pad1)") (class "Default")
      (node (ref "P247") (pin "1") (pinfunction "P_1") (pintype "passive"))
    )
    (net (code "177") (name "unconnected-(P248-P-Pad1)") (class "Default")
      (node (ref "P248") (pin "1") (pinfunction "P_1") (pintype "passive"))
    )
    (net (code "178") (name "unconnected-(P249-P-Pad1)") (class "Default")
      (node (ref "P249") (pin "1") (pinfunction "P_1") (pintype "passive"))
    )
    (net (code "179") (name "unconnected-(P250-P-Pad1)") (class "Default")
      (node (ref "P250") (pin "1") (pinfunction "P_1") (pintype "passive"))
    )
    (net (code "180") (name "unconnected-(P251-P-Pad1)") (class "Default")
      (node (ref "P251") (pin "1") (pinfunction "P_1") (pintype "passive"))
    )
    (net (code "181") (name "unconnected-(P252-P-Pad1)") (class "Default")
      (node (ref "P252") (pin "1") (pinfunction "P_1") (pintype "passive"))
    )
    (net (code "182") (name "unconnected-(P253-P-Pad1)") (class "Default")
      (node (ref "P253") (pin "1") (pinfunction "P_1") (pintype "passive"))
    )
    (net (code "183") (name "unconnected-(P254-P-Pad1)") (class "Default")
      (node (ref "P254") (pin "1") (pinfunction "P_1") (pintype "passive"))
    )
    (net (code "184") (name "unconnected-(P255-P-Pad1)") (class "Default")
      (node (ref "P255") (pin "1") (pinfunction "P_1") (pintype "passive"))
    )
    (net (code "185") (name "unconnected-(P256-P-Pad1)") (class "Default")
      (node (ref "P256") (pin "1") (pinfunction "P_1") (pintype "passive"))
    )
    (net (code "186") (name "unconnected-(P257-P-Pad1)") (class "Default")
      (node (ref "P257") (pin "1") (pinfunction "P_1") (pintype "passive"))
    )
    (net (code "187") (name "unconnected-(P258-P-Pad1)") (class "Default")
      (node (ref "P258") (pin "1") (pinfunction "P_1") (pintype "passive"))
    )
    (net (code "188") (name "unconnected-(P259-P-Pad1)") (class "Default")
      (node (ref "P259") (pin "1") (pinfunction "P_1") (pintype "passive"))
    )
    (net (code "189") (name "unconnected-(P260-P-Pad1)") (class "Default")
      (node (ref "P260") (pin "1") (pinfunction "P_1") (pintype "passive"))
    )
    (net (code "190") (name "unconnected-(P261-P-Pad1)") (class "Default")
      (node (ref "P261") (pin "1") (pinfunction "P_1") (pintype "passive"))
    )
    (net (code "191") (name "unconnected-(P262-P-Pad1)") (class "Default")
      (node (ref "P262") (pin "1") (pinfunction "P_1") (pintype "passive"))
    )
    (net (code "192") (name "unconnected-(P263-P-Pad1)") (class "Default")
      (node (ref "P263") (pin "1") (pinfunction "P_1") (pintype "passive"))
    )
    (net (code "193") (name "unconnected-(P264-P-Pad1)") (class "Default")
      (node (ref "P264") (pin "1") (pinfunction "P_1") (pintype "passive"))
    )
    (net (code "194") (name "unconnected-(P265-P-Pad1)") (class "Default")
      (node (ref "P265") (pin "1") (pinfunction "P_1") (pintype "passive"))
    )
    (net (code "195") (name "unconnected-(P266-P-Pad1)") (class "Default")
      (node (ref "P266") (pin "1") (pinfunction "P_1") (pintype "passive"))
    )
    (net (code "196") (name "unconnected-(P267-P-Pad1)") (class "Default")
      (node (ref "P267") (pin "1") (pinfunction "P_1") (pintype "passive"))
    )
    (net (code "197") (name "unconnected-(P268-P-Pad1)") (class "Default")
      (node (ref "P268") (pin "1") (pinfunction "P_1") (pintype "passive"))
    )
    (net (code "198") (name "unconnected-(P269-P-Pad1)") (class "Default")
      (node (ref "P269") (pin "1") (pinfunction "P_1") (pintype "passive"))
    )
    (net (code "199") (name "unconnected-(P270-P-Pad1)") (class "Default")
      (node (ref "P270") (pin "1") (pinfunction "P_1") (pintype "passive"))
    )
    (net (code "200") (name "unconnected-(P271-P-Pad1)") (class "Default")
      (node (ref "P271") (pin "1") (pinfunction "P_1") (pintype "passive"))
    )
    (net (code "201") (name "unconnected-(P272-P-Pad1)") (class "Default")
      (node (ref "P272") (pin "1") (pinfunction "P_1") (pintype "passive"))
    )
    (net (code "202") (name "unconnected-(P273-P-Pad1)") (class "Default")
      (node (ref "P273") (pin "1") (pinfunction "P_1") (pintype "passive"))
    )
    (net (code "203") (name "unconnected-(P274-P-Pad1)") (class "Default")
      (node (ref "P274") (pin "1") (pinfunction "P_1") (pintype "passive"))
    )
    (net (code "204") (name "unconnected-(P275-P-Pad1)") (class "Default")
      (node (ref "P275") (pin "1") (pinfunction "P_1") (pintype "passive"))
    )
    (net (code "205") (name "unconnected-(P276-P-Pad1)") (class "Default")
      (node (ref "P276") (pin "1") (pinfunction "P_1") (pintype "passive"))
    )
    (net (code "206") (name "unconnected-(P277-P-Pad1)") (class "Default")
      (node (ref "P277") (pin "1") (pinfunction "P_1") (pintype "passive"))
    )
    (net (code "207") (name "unconnected-(P278-P-Pad1)") (class "Default")
      (node (ref "P278") (pin "1") (pinfunction "P_1") (pintype "passive"))
    )
    (net (code "208") (name "unconnected-(P279-P-Pad1)") (class "Default")
      (node (ref "P279") (pin "1") (pinfunction "P_1") (pintype "passive"))
    )
    (net (code "209") (name "unconnected-(P280-P-Pad1)") (class "Default")
      (node (ref "P280") (pin "1") (pinfunction "P_1") (pintype "passive"))
    )
    (net (code "210") (name "unconnected-(P281-P-Pad1)") (class "Default")
      (node (ref "P281") (pin "1") (pinfunction "P_1") (pintype "passive"))
    )
    (net (code "211") (name "unconnected-(P282-P-Pad1)") (class "Default")
      (node (ref "P282") (pin "1") (pinfunction "P_1") (pintype "passive"))
    )
    (net (code "212") (name "unconnected-(P283-P-Pad1)") (class "Default")
      (node (ref "P283") (pin "1") (pinfunction "P_1") (pintype "passive"))
    )
    (net (code "213") (name "unconnected-(P284-P-Pad1)") (class "Default")
      (node (ref "P284") (pin "1") (pinfunction "P_1") (pintype "passive"))
    )
    (net (code "214") (name "unconnected-(P285-P-Pad1)") (class "Default")
      (node (ref "P285") (pin "1") (pinfunction "P_1") (pintype "passive"))
    )
    (net (code "215") (name "unconnected-(P286-P-Pad1)") (class "Default")
      (node (ref "P286") (pin "1") (pinfunction "P_1") (pintype "passive"))
    )
    (net (code "216") (name "unconnected-(P287-P-Pad1)") (class "Default")
      (node (ref "P287") (pin "1") (pinfunction "P_1") (pintype "passive"))
    )
    (net (code "217") (name "unconnected-(P288-P-Pad1)") (class "Default")
      (node (ref "P288") (pin "1") (pinfunction "P_1") (pintype "passive"))
    )
    (net (code "218") (name "unconnected-(P289-P-Pad1)") (class "Default")
      (node (ref "P289") (pin "1") (pinfunction "P_1") (pintype "passive"))
    )
    (net (code "219") (name "unconnected-(P290-P-Pad1)") (class "Default")
      (node (ref "P290") (pin "1") (pinfunction "P_1") (pintype "passive"))
    )
    (net (code "220") (name "unconnected-(P291-P-Pad1)") (class "Default")
      (node (ref "P291") (pin "1") (pinfunction "P_1") (pintype "passive"))
    )
    (net (code "221") (name "unconnected-(P292-P-Pad1)") (class "Default")
      (node (ref "P292") (pin "1") (pinfunction "P_1") (pintype "passive"))
    )
    (net (code "222") (name "unconnected-(P293-P-Pad1)") (class "Default")
      (node (ref "P293") (pin "1") (pinfunction "P_1") (pintype "passive"))
    )
    (net (code "223") (name "unconnected-(P294-P-Pad1)") (class "Default")
      (node (ref "P294") (pin "1") (pinfunction "P_1") (pintype "passive"))
    )
    (net (code "224") (name "unconnected-(P295-P-Pad1)") (class "Default")
      (node (ref "P295") (pin "1") (pinfunction "P_1") (pintype "passive"))
    )
    (net (code "225") (name "unconnected-(P296-P-Pad1)") (class "Default")
      (node (ref "P296") (pin "1") (pinfunction "P_1") (pintype "passive"))
    )
    (net (code "226") (name "unconnected-(P297-P-Pad1)") (class "Default")
      (node (ref "P297") (pin "1") (pinfunction "P_1") (pintype "passive"))
    )
    (net (code "227") (name "unconnected-(P298-P-Pad1)") (class "Default")
      (node (ref "P298") (pin "1") (pinfunction "P_1") (pintype "passive"))
    )
    (net (code "228") (name "unconnected-(P299-P-Pad1)") (class "Default")
      (node (ref "P299") (pin "1") (pinfunction "P_1") (pintype "passive"))
    )
    (net (code "229") (name "unconnected-(P300-P-Pad1)") (class "Default")
      (node (ref "P300") (pin "1") (pinfunction "P_1") (pintype "passive"))
    )
    (net (code "230") (name "unconnected-(P301-P-Pad1)") (class "Default")
      (node (ref "P301") (pin "1") (pinfunction "P_1") (pintype "passive"))
    )
    (net (code "231") (name "unconnected-(P302-P-Pad1)") (class "Default")
      (node (ref "P302") (pin "1") (pinfunction "P_1") (pintype "passive"))
    )
    (net (code "232") (name "unconnected-(P303-P-Pad1)") (class "Default")
      (node (ref "P303") (pin "1") (pinfunction "P_1") (pintype "passive"))
    )
    (net (code "233") (name "unconnected-(P304-P-Pad1)") (class "Default")
      (node (ref "P304") (pin "1") (pinfunction "P_1") (pintype "passive"))
    )
    (net (code "234") (name "unconnected-(P305-P-Pad1)") (class "Default")
      (node (ref "P305") (pin "1") (pinfunction "P_1") (pintype "passive"))
    )
    (net (code "235") (name "unconnected-(P306-P-Pad1)") (class "Default")
      (node (ref "P306") (pin "1") (pinfunction "P_1") (pintype "passive"))
    )
    (net (code "236") (name "unconnected-(P307-P-Pad1)") (class "Default")
      (node (ref "P307") (pin "1") (pinfunction "P_1") (pintype "passive"))
    )
    (net (code "237") (name "unconnected-(P308-P-Pad1)") (class "Default")
      (node (ref "P308") (pin "1") (pinfunction "P_1") (pintype "passive"))
    )
    (net (code "238") (name "unconnected-(P309-P-Pad1)") (class "Default")
      (node (ref "P309") (pin "1") (pinfunction "P_1") (pintype "passive"))
    )
    (net (code "239") (name "unconnected-(P310-P-Pad1)") (class "Default")
      (node (ref "P310") (pin "1") (pinfunction "P_1") (pintype "passive"))
    )
    (net (code "240") (name "unconnected-(P311-P-Pad1)") (class "Default")
      (node (ref "P311") (pin "1") (pinfunction "P_1") (pintype "passive"))
    )
    (net (code "241") (name "unconnected-(P312-P-Pad1)") (class "Default")
      (node (ref "P312") (pin "1") (pinfunction "P_1") (pintype "passive"))
    )
    (net (code "242") (name "unconnected-(P313-P-Pad1)") (class "Default")
      (node (ref "P313") (pin "1") (pinfunction "P_1") (pintype "passive"))
    )
    (net (code "243") (name "unconnected-(P314-P-Pad1)") (class "Default")
      (node (ref "P314") (pin "1") (pinfunction "P_1") (pintype "passive"))
    )
    (net (code "244") (name "unconnected-(P315-P-Pad1)") (class "Default")
      (node (ref "P315") (pin "1") (pinfunction "P_1") (pintype "passive"))
    )
    (net (code "245") (name "unconnected-(P316-P-Pad1)") (class "Default")
      (node (ref "P316") (pin "1") (pinfunction "P_1") (pintype "passive"))
    )
    (net (code "246") (name "unconnected-(P317-P-Pad1)") (class "Default")
      (node (ref "P317") (pin "1") (pinfunction "P_1") (pintype "passive"))
    )
    (net (code "247") (name "unconnected-(P318-P-Pad1)") (class "Default")
      (node (ref "P318") (pin "1") (pinfunction "P_1") (pintype "passive"))
    )
    (net (code "248") (name "unconnected-(P319-P-Pad1)") (class "Default")
      (node (ref "P319") (pin "1") (pinfunction "P_1") (pintype "passive"))
    )
    (net (code "249") (name "unconnected-(P320-P-Pad1)") (class "Default")
      (node (ref "P320") (pin "1") (pinfunction "P_1") (pintype "passive"))
    )
    (net (code "250") (name "unconnected-(P321-P-Pad1)") (class "Default")
      (node (ref "P321") (pin "1") (pinfunction "P_1") (pintype "passive"))
    )
    (net (code "251") (name "unconnected-(P322-P-Pad1)") (class "Default")
      (node (ref "P322") (pin "1") (pinfunction "P_1") (pintype "passive"))
    )
    (net (code "252") (name "unconnected-(P323-P-Pad1)") (class "Default")
      (node (ref "P323") (pin "1") (pinfunction "P_1") (pintype "passive"))
    )
    (net (code "253") (name "unconnected-(P324-P-Pad1)") (class "Default")
      (node (ref "P324") (pin "1") (pinfunction "P_1") (pintype "passive"))
    )
    (net (code "254") (name "unconnected-(P325-P-Pad1)") (class "Default")
      (node (ref "P325") (pin "1") (pinfunction "P_1") (pintype "passive"))
    )
    (net (code "255") (name "unconnected-(P326-P-Pad1)") (class "Default")
      (node (ref "P326") (pin "1") (pinfunction "P_1") (pintype "passive"))
    )
    (net (code "256") (name "unconnected-(P327-P-Pad1)") (class "Default")
      (node (ref "P327") (pin "1") (pinfunction "P_1") (pintype "passive"))
    )
    (net (code "257") (name "unconnected-(P328-P-Pad1)") (class "Default")
      (node (ref "P328") (pin "1") (pinfunction "P_1") (pintype "passive"))
    )
    (net (code "258") (name "unconnected-(P329-P-Pad1)") (class "Default")
      (node (ref "P329") (pin "1") (pinfunction "P_1") (pintype "passive"))
    )
    (net (code "259") (name "unconnected-(P330-P-Pad1)") (class "Default")
      (node (ref "P330") (pin "1") (pinfunction "P_1") (pintype "passive"))
    )
    (net (code "260") (name "unconnected-(P331-P-Pad1)") (class "Default")
      (node (ref "P331") (pin "1") (pinfunction "P_1") (pintype "passive"))
    )
    (net (code "261") (name "unconnected-(P332-P-Pad1)") (class "Default")
      (node (ref "P332") (pin "1") (pinfunction "P_1") (pintype "passive"))
    )
    (net (code "262") (name "unconnected-(P333-P-Pad1)") (class "Default")
      (node (ref "P333") (pin "1") (pinfunction "P_1") (pintype "passive"))
    )
    (net (code "263") (name "unconnected-(P334-P-Pad1)") (class "Default")
      (node (ref "P334") (pin "1") (pinfunction "P_1") (pintype "passive"))
    )
    (net (code "264") (name "unconnected-(P335-P-Pad1)") (class "Default")
      (node (ref "P335") (pin "1") (pinfunction "P_1") (pintype "passive"))
    )
    (net (code "265") (name "unconnected-(P336-P-Pad1)") (class "Default")
      (node (ref "P336") (pin "1") (pinfunction "P_1") (pintype "passive"))
    )
    (net (code "266") (name "unconnected-(P337-P-Pad1)") (class "Default")
      (node (ref "P337") (pin "1") (pinfunction "P_1") (pintype "passive"))
    )
    (net (code "267") (name "unconnected-(P338-P-Pad1)") (class "Default")
      (node (ref "P338") (pin "1") (pinfunction "P_1") (pintype "passive"))
    )
    (net (code "268") (name "unconnected-(P339-P-Pad1)") (class "Default")
      (node (ref "P339") (pin "1") (pinfunction "P_1") (pintype "passive"))
    )
    (net (code "269") (name "unconnected-(P340-P-Pad1)") (class "Default")
      (node (ref "P340") (pin "1") (pinfunction "P_1") (pintype "passive"))
    )
    (net (code "270") (name "unconnected-(P341-P-Pad1)") (class "Default")
      (node (ref "P341") (pin "1") (pinfunction "P_1") (pintype "passive"))
    )
    (net (code "271") (name "unconnected-(P342-P-Pad1)") (class "Default")
      (node (ref "P342") (pin "1") (pinfunction "P_1") (pintype "passive"))
    )
    (net (code "272") (name "unconnected-(P343-P-Pad1)") (class "Default")
      (node (ref "P343") (pin "1") (pinfunction "P_1") (pintype "passive"))
    )
    (net (code "273") (name "unconnected-(P344-P-Pad1)") (class "Default")
      (node (ref "P344") (pin "1") (pinfunction "P_1") (pintype "passive"))
    )
    (net (code "274") (name "unconnected-(P345-P-Pad1)") (class "Default")
      (node (ref "P345") (pin "1") (pinfunction "P_1") (pintype "passive"))
    )
    (net (code "275") (name "unconnected-(P346-P-Pad1)") (class "Default")
      (node (ref "P346") (pin "1") (pinfunction "P_1") (pintype "passive"))
    )
    (net (code "276") (name "unconnected-(P347-P-Pad1)") (class "Default")
      (node (ref "P347") (pin "1") (pinfunction "P_1") (pintype "passive"))
    )
    (net (code "277") (name "unconnected-(P348-P-Pad1)") (class "Default")
      (node (ref "P348") (pin "1") (pinfunction "P_1") (pintype "passive"))
    )
    (net (code "278") (name "unconnected-(P349-P-Pad1)") (class "Default")
      (node (ref "P349") (pin "1") (pinfunction "P_1") (pintype "passive"))
    )
    (net (code "279") (name "unconnected-(P350-P-Pad1)") (class "Default")
      (node (ref "P350") (pin "1") (pinfunction "P_1") (pintype "passive"))
    )
    (net (code "280") (name "unconnected-(P351-P-Pad1)") (class "Default")
      (node (ref "P351") (pin "1") (pinfunction "P_1") (pintype "passive"))
    )
    (net (code "281") (name "unconnected-(P352-P-Pad1)") (class "Default")
      (node (ref "P352") (pin "1") (pinfunction "P_1") (pintype "passive"))
    )
    (net (code "282") (name "unconnected-(P353-P-Pad1)") (class "Default")
      (node (ref "P353") (pin "1") (pinfunction "P_1") (pintype "passive"))
    )
    (net (code "283") (name "unconnected-(P354-P-Pad1)") (class "Default")
      (node (ref "P354") (pin "1") (pinfunction "P_1") (pintype "passive"))
    )
    (net (code "284") (name "unconnected-(P355-P-Pad1)") (class "Default")
      (node (ref "P355") (pin "1") (pinfunction "P_1") (pintype "passive"))
    )
    (net (code "285") (name "unconnected-(P356-P-Pad1)") (class "Default")
      (node (ref "P356") (pin "1") (pinfunction "P_1") (pintype "passive"))
    )
    (net (code "286") (name "unconnected-(P357-P-Pad1)") (class "Default")
      (node (ref "P357") (pin "1") (pinfunction "P_1") (pintype "passive"))
    )
    (net (code "287") (name "unconnected-(P358-P-Pad1)") (class "Default")
      (node (ref "P358") (pin "1") (pinfunction "P_1") (pintype "passive"))
    )
    (net (code "288") (name "unconnected-(P359-P-Pad1)") (class "Default")
      (node (ref "P359") (pin "1") (pinfunction "P_1") (pintype "passive"))
    )
    (net (code "289") (name "unconnected-(P360-P-Pad1)") (class "Default")
      (node (ref "P360") (pin "1") (pinfunction "P_1") (pintype "passive"))
    )
    (net (code "290") (name "unconnected-(P361-P-Pad1)") (class "Default")
      (node (ref "P361") (pin "1") (pinfunction "P_1") (pintype "passive"))
    )
    (net (code "291") (name "unconnected-(P362-P-Pad1)") (class "Default")
      (node (ref "P362") (pin "1") (pinfunction "P_1") (pintype "passive"))
    )
    (net (code "292") (name "unconnected-(P363-P-Pad1)") (class "Default")
      (node (ref "P363") (pin "1") (pinfunction "P_1") (pintype "passive"))
    )
    (net (code "293") (name "unconnected-(P364-P-Pad1)") (class "Default")
      (node (ref "P364") (pin "1") (pinfunction "P_1") (pintype "passive"))
    )
    (net (code "294") (name "unconnected-(P365-P-Pad1)") (class "Default")
      (node (ref "P365") (pin "1") (pinfunction "P_1") (pintype "passive"))
    )
    (net (code "295") (name "unconnected-(P366-P-Pad1)") (class "Default")
      (node (ref "P366") (pin "1") (pinfunction "P_1") (pintype "passive"))
    )
    (net (code "296") (name "unconnected-(P367-P-Pad1)") (class "Default")
      (node (ref "P367") (pin "1") (pinfunction "P_1") (pintype "passive"))
    )
    (net (code "297") (name "unconnected-(P368-P-Pad1)") (class "Default")
      (node (ref "P368") (pin "1") (pinfunction "P_1") (pintype "passive"))
    )
    (net (code "298") (name "unconnected-(P369-P-Pad1)") (class "Default")
      (node (ref "P369") (pin "1") (pinfunction "P_1") (pintype "passive"))
    )
    (net (code "299") (name "unconnected-(P370-P-Pad1)") (class "Default")
      (node (ref "P370") (pin "1") (pinfunction "P_1") (pintype "passive"))
    )
    (net (code "300") (name "unconnected-(P371-P-Pad1)") (class "Default")
      (node (ref "P371") (pin "1") (pinfunction "P_1") (pintype "passive"))
    )
    (net (code "301") (name "unconnected-(P372-P-Pad1)") (class "Default")
      (node (ref "P372") (pin "1") (pinfunction "P_1") (pintype "passive"))
    )
    (net (code "302") (name "unconnected-(P373-P-Pad1)") (class "Default")
      (node (ref "P373") (pin "1") (pinfunction "P_1") (pintype "passive"))
    )
    (net (code "303") (name "unconnected-(P374-P-Pad1)") (class "Default")
      (node (ref "P374") (pin "1") (pinfunction "P_1") (pintype "passive"))
    )
    (net (code "304") (name "unconnected-(P375-P-Pad1)") (class "Default")
      (node (ref "P375") (pin "1") (pinfunction "P_1") (pintype "passive"))
    )
    (net (code "305") (name "unconnected-(P376-P-Pad1)") (class "Default")
      (node (ref "P376") (pin "1") (pinfunction "P_1") (pintype "passive"))
    )
    (net (code "306") (name "unconnected-(P377-P-Pad1)") (class "Default")
      (node (ref "P377") (pin "1") (pinfunction "P_1") (pintype "passive"))
    )
    (net (code "307") (name "unconnected-(P378-P-Pad1)") (class "Default")
      (node (ref "P378") (pin "1") (pinfunction "P_1") (pintype "passive"))
    )
    (net (code "308") (name "unconnected-(P379-P-Pad1)") (class "Default")
      (node (ref "P379") (pin "1") (pinfunction "P_1") (pintype "passive"))
    )
    (net (code "309") (name "unconnected-(P380-P-Pad1)") (class "Default")
      (node (ref "P380") (pin "1") (pinfunction "P_1") (pintype "passive"))
    )
    (net (code "310") (name "unconnected-(P381-P-Pad1)") (class "Default")
      (node (ref "P381") (pin "1") (pinfunction "P_1") (pintype "passive"))
    )
    (net (code "311") (name "unconnected-(P382-P-Pad1)") (class "Default")
      (node (ref "P382") (pin "1") (pinfunction "P_1") (pintype "passive"))
    )
    (net (code "312") (name "unconnected-(P383-P-Pad1)") (class "Default")
      (node (ref "P383") (pin "1") (pinfunction "P_1") (pintype "passive"))
    )
    (net (code "313") (name "unconnected-(P384-P-Pad1)") (class "Default")
      (node (ref "P384") (pin "1") (pinfunction "P_1") (pintype "passive"))
    )
    (net (code "314") (name "unconnected-(P385-P-Pad1)") (class "Default")
      (node (ref "P385") (pin "1") (pinfunction "P_1") (pintype "passive"))
    )
    (net (code "315") (name "unconnected-(P386-P-Pad1)") (class "Default")
      (node (ref "P386") (pin "1") (pinfunction "P_1") (pintype "passive"))
    )
    (net (code "316") (name "unconnected-(P387-P-Pad1)") (class "Default")
      (node (ref "P387") (pin "1") (pinfunction "P_1") (pintype "passive"))
    )
    (net (code "317") (name "unconnected-(P388-P-Pad1)") (class "Default")
      (node (ref "P388") (pin "1") (pinfunction "P_1") (pintype "passive"))
    )
    (net (code "318") (name "unconnected-(P389-P-Pad1)") (class "Default")
      (node (ref "P389") (pin "1") (pinfunction "P_1") (pintype "passive"))
    )
    (net (code "319") (name "unconnected-(P390-P-Pad1)") (class "Default")
      (node (ref "P390") (pin "1") (pinfunction "P_1") (pintype "passive"))
    )
    (net (code "320") (name "unconnected-(P391-P-Pad1)") (class "Default")
      (node (ref "P391") (pin "1") (pinfunction "P_1") (pintype "passive"))
    )
    (net (code "321") (name "unconnected-(P392-P-Pad1)") (class "Default")
      (node (ref "P392") (pin "1") (pinfunction "P_1") (pintype "passive"))
    )
    (net (code "322") (name "unconnected-(P393-P-Pad1)") (class "Default")
      (node (ref "P393") (pin "1") (pinfunction "P_1") (pintype "passive"))
    )
    (net (code "323") (name "unconnected-(P394-P-Pad1)") (class "Default")
      (node (ref "P394") (pin "1") (pinfunction "P_1") (pintype "passive"))
    )
    (net (code "324") (name "unconnected-(P395-P-Pad1)") (class "Default")
      (node (ref "P395") (pin "1") (pinfunction "P_1") (pintype "passive"))
    )
    (net (code "325") (name "unconnected-(P396-P-Pad1)") (class "Default")
      (node (ref "P396") (pin "1") (pinfunction "P_1") (pintype "passive"))
    )
    (net (code "326") (name "unconnected-(P397-P-Pad1)") (class "Default")
      (node (ref "P397") (pin "1") (pinfunction "P_1") (pintype "passive"))
    )
    (net (code "327") (name "unconnected-(P398-P-Pad1)") (class "Default")
      (node (ref "P398") (pin "1") (pinfunction "P_1") (pintype "passive"))
    )
    (net (code "328") (name "unconnected-(P399-P-Pad1)") (class "Default")
      (node (ref "P399") (pin "1") (pinfunction "P_1") (pintype "passive"))
    )
    (net (code "329") (name "unconnected-(P400-P-Pad1)") (class "Default")
      (node (ref "P400") (pin "1") (pinfunction "P_1") (pintype "passive"))
    )
    (net (code "330") (name "unconnected-(P401-P-Pad1)") (class "Default")
      (node (ref "P401") (pin "1") (pinfunction "P_1") (pintype "passive"))
    )
    (net (code "331") (name "unconnected-(P402-P-Pad1)") (class "Default")
      (node (ref "P402") (pin "1") (pinfunction "P_1") (pintype "passive"))
    )
    (net (code "332") (name "unconnected-(P403-P-Pad1)") (class "Default")
      (node (ref "P403") (pin "1") (pinfunction "P_1") (pintype "passive"))
    )
    (net (code "333") (name "unconnected-(P404-P-Pad1)") (class "Default")
      (node (ref "P404") (pin "1") (pinfunction "P_1") (pintype "passive"))
    )
    (net (code "334") (name "unconnected-(P405-P-Pad1)") (class "Default")
      (node (ref "P405") (pin "1") (pinfunction "P_1") (pintype "passive"))
    )
    (net (code "335") (name "unconnected-(P406-P-Pad1)") (class "Default")
      (node (ref "P406") (pin "1") (pinfunction "P_1") (pintype "passive"))
    )
    (net (code "336") (name "unconnected-(P407-P-Pad1)") (class "Default")
      (node (ref "P407") (pin "1") (pinfunction "P_1") (pintype "passive"))
    )
    (net (code "337") (name "unconnected-(P408-P-Pad1)") (class "Default")
      (node (ref "P408") (pin "1") (pinfunction "P_1") (pintype "passive"))
    )
    (net (code "338") (name "unconnected-(P409-P-Pad1)") (class "Default")
      (node (ref "P409") (pin "1") (pinfunction "P_1") (pintype "passive"))
    )
    (net (code "339") (name "unconnected-(P410-P-Pad1)") (class "Default")
      (node (ref "P410") (pin "1") (pinfunction "P_1") (pintype "passive"))
    )
    (net (code "340") (name "unconnected-(P411-P-Pad1)") (class "Default")
      (node (ref "P411") (pin "1") (pinfunction "P_1") (pintype "passive"))
    )
    (net (code "341") (name "unconnected-(P412-P-Pad1)") (class "Default")
      (node (ref "P412") (pin "1") (pinfunction "P_1") (pintype "passive"))
    )
    (net (code "342") (name "unconnected-(U$4-IOB1-PadB1)") (class "Default")
      (node (ref "U$4") (pin "B1") (pinfunction "IOB1_B1") (pintype "bidirectional"))
    )
    (net (code "343") (name "unconnected-(U$4-IOB2-PadB2)") (class "Default")
      (node (ref "U$4") (pin "B2") (pinfunction "IOB2_B2") (pintype "bidirectional"))
    )
    (net (code "344") (name "unconnected-(U2-OSCI-Pad27)") (class "Default")
      (node (ref "U2") (pin "27") (pinfunction "OSCI_27") (pintype "input"))
    )
    (net (code "345") (name "unconnected-(U2-OSCO-Pad28)") (class "Default")
      (node (ref "U2") (pin "28") (pinfunction "OSCO_28") (pintype "output"))
    )
    (net (code "346") (name "unconnected-(U2-PWREN-Pad14)") (class "Default")
      (node (ref "U2") (pin "14") (pinfunction "PWREN_14") (pintype "input"))
    )
    (net (code "347") (name "unconnected-(U2-SLEEP-Pad12)") (class "Default")
      (node (ref "U2") (pin "12") (pinfunction "SLEEP_12") (pintype "input"))
    )
    (net (code "348") (name "unconnected-(U2-TXDEN-Pad13)") (class "Default")
      (node (ref "U2") (pin "13") (pinfunction "TXDEN_13") (pintype "input"))
    )
  )
)
